# XMICRO-SERIAL_V1_1.net
KiCad netlist of a schematic drawn in EAGLE
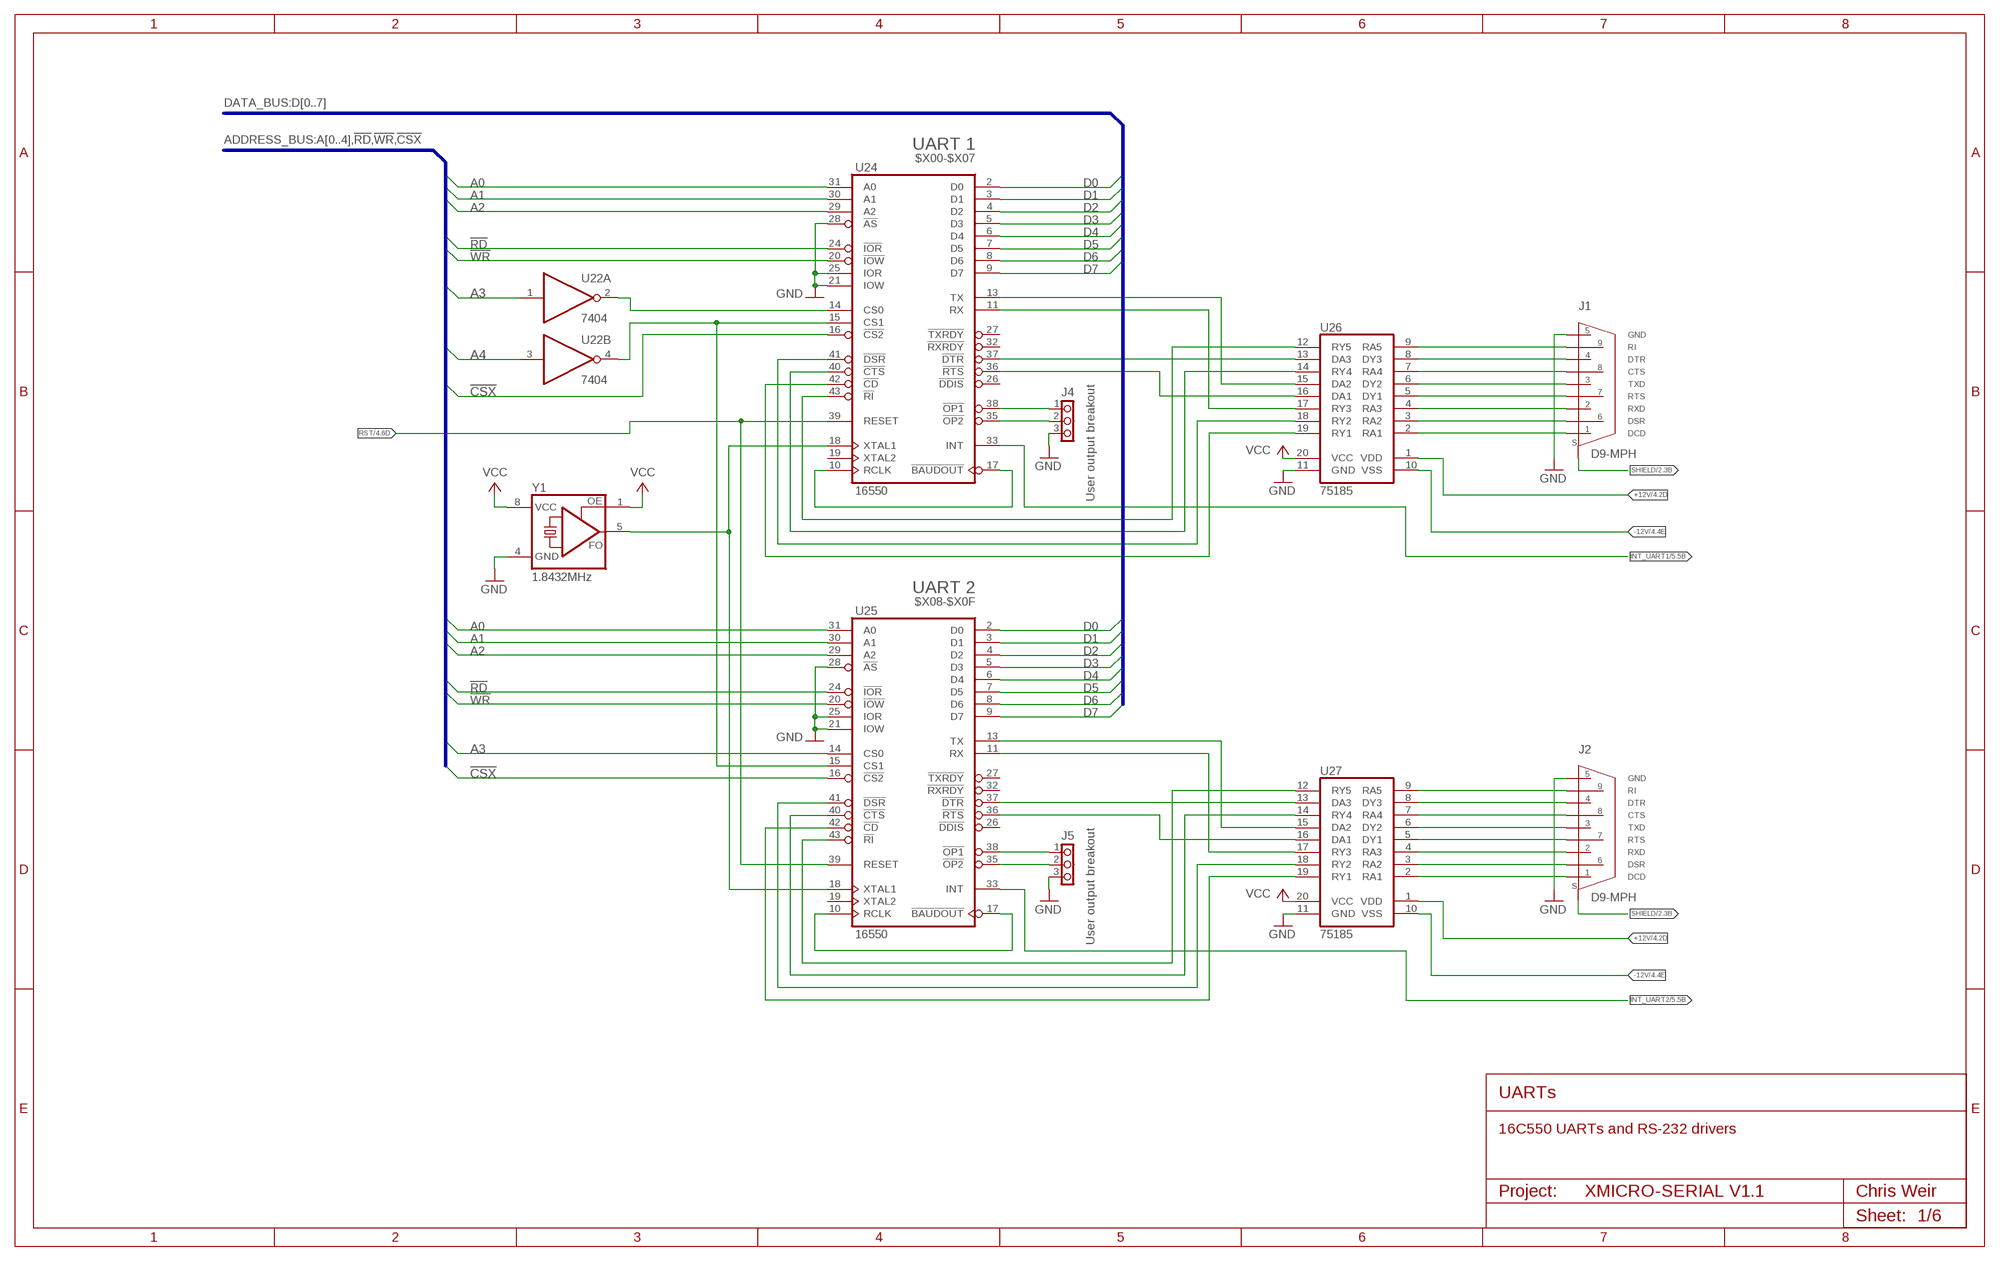
[diagram p0: schematic, sheet 1]
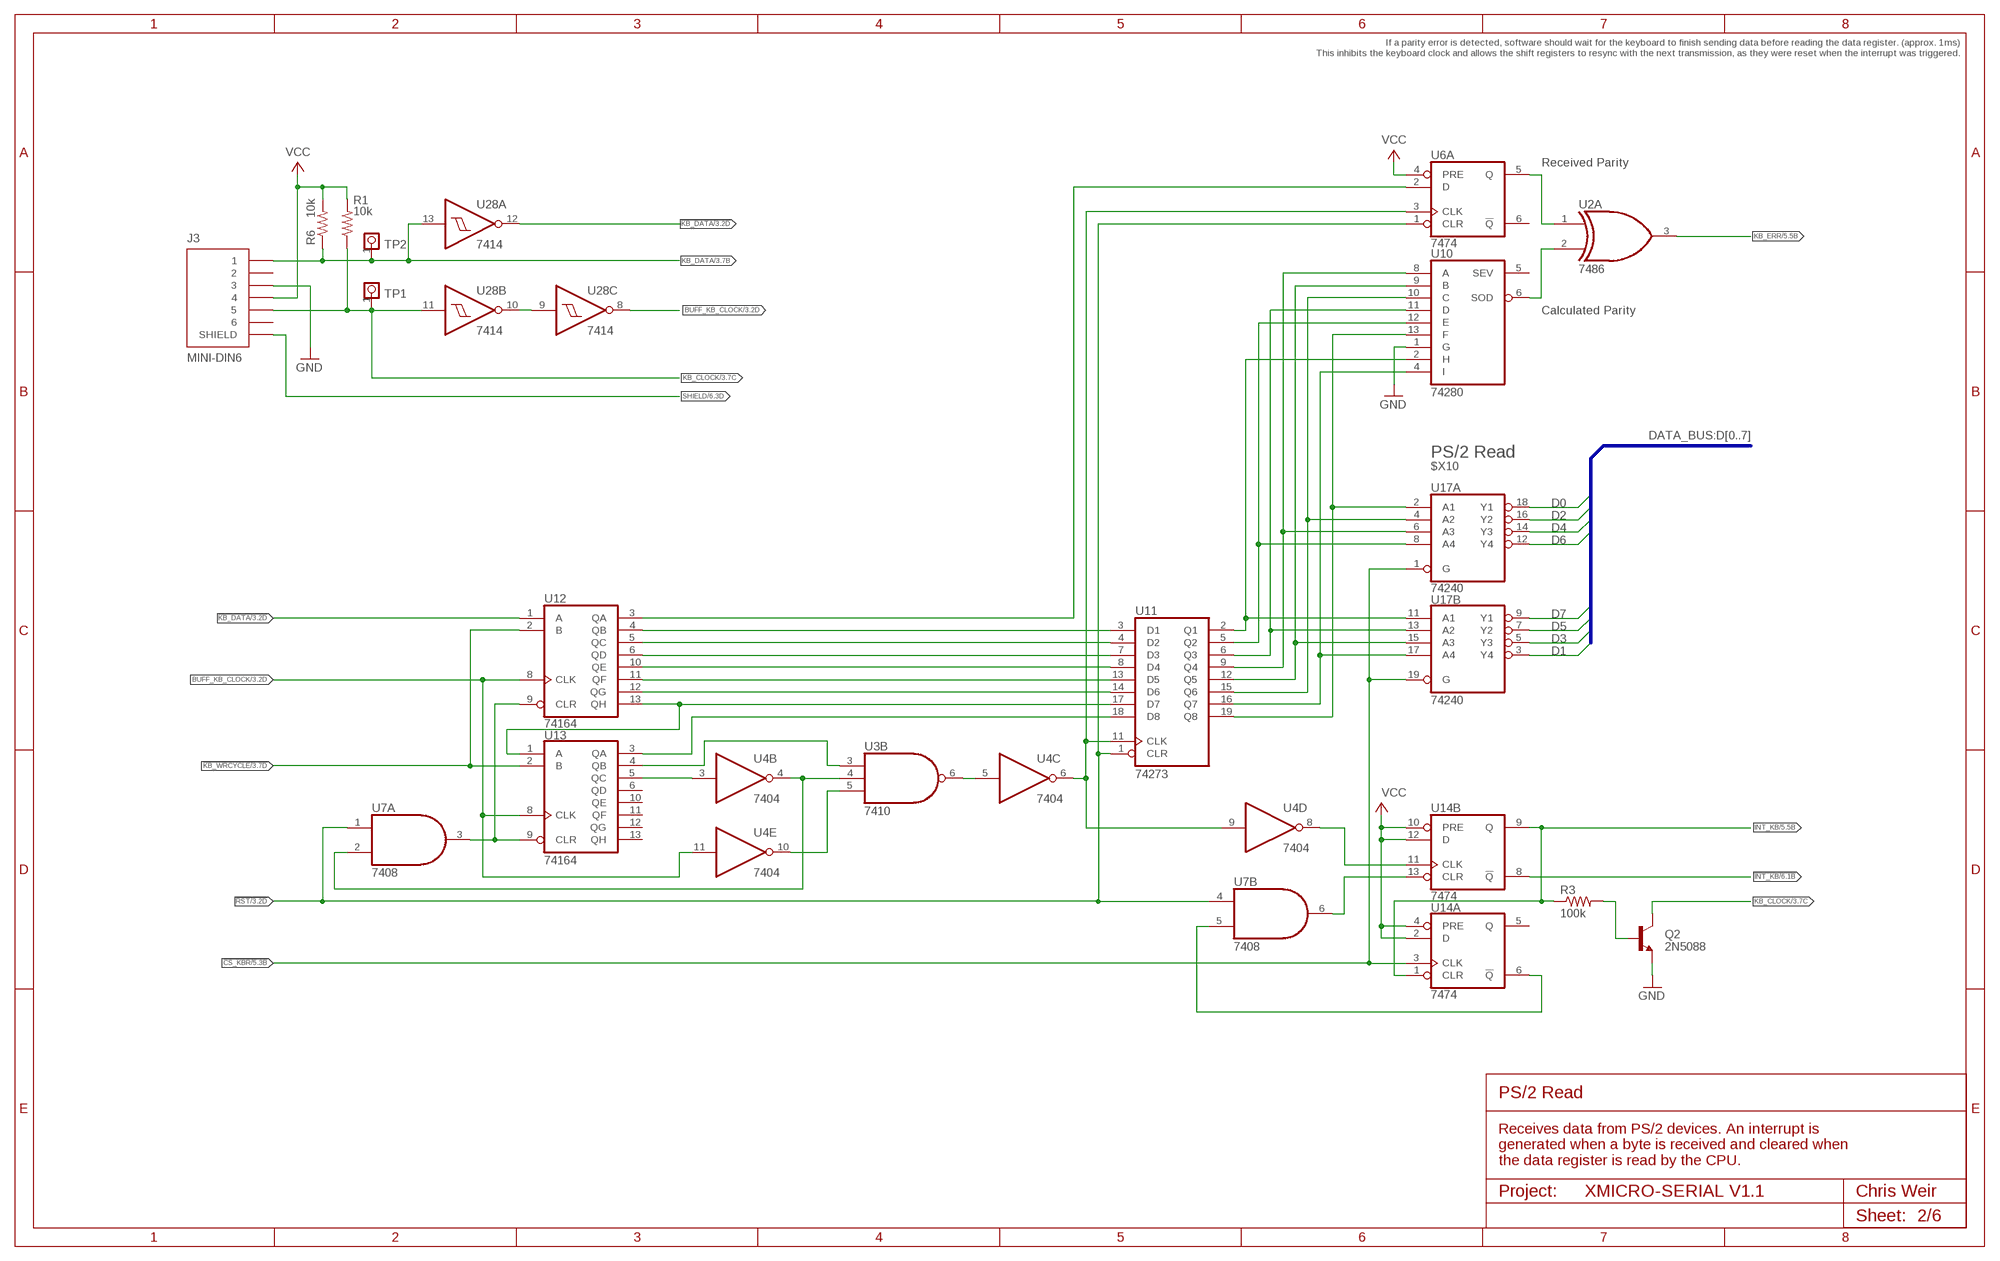
[diagram p1: schematic, sheet 2]
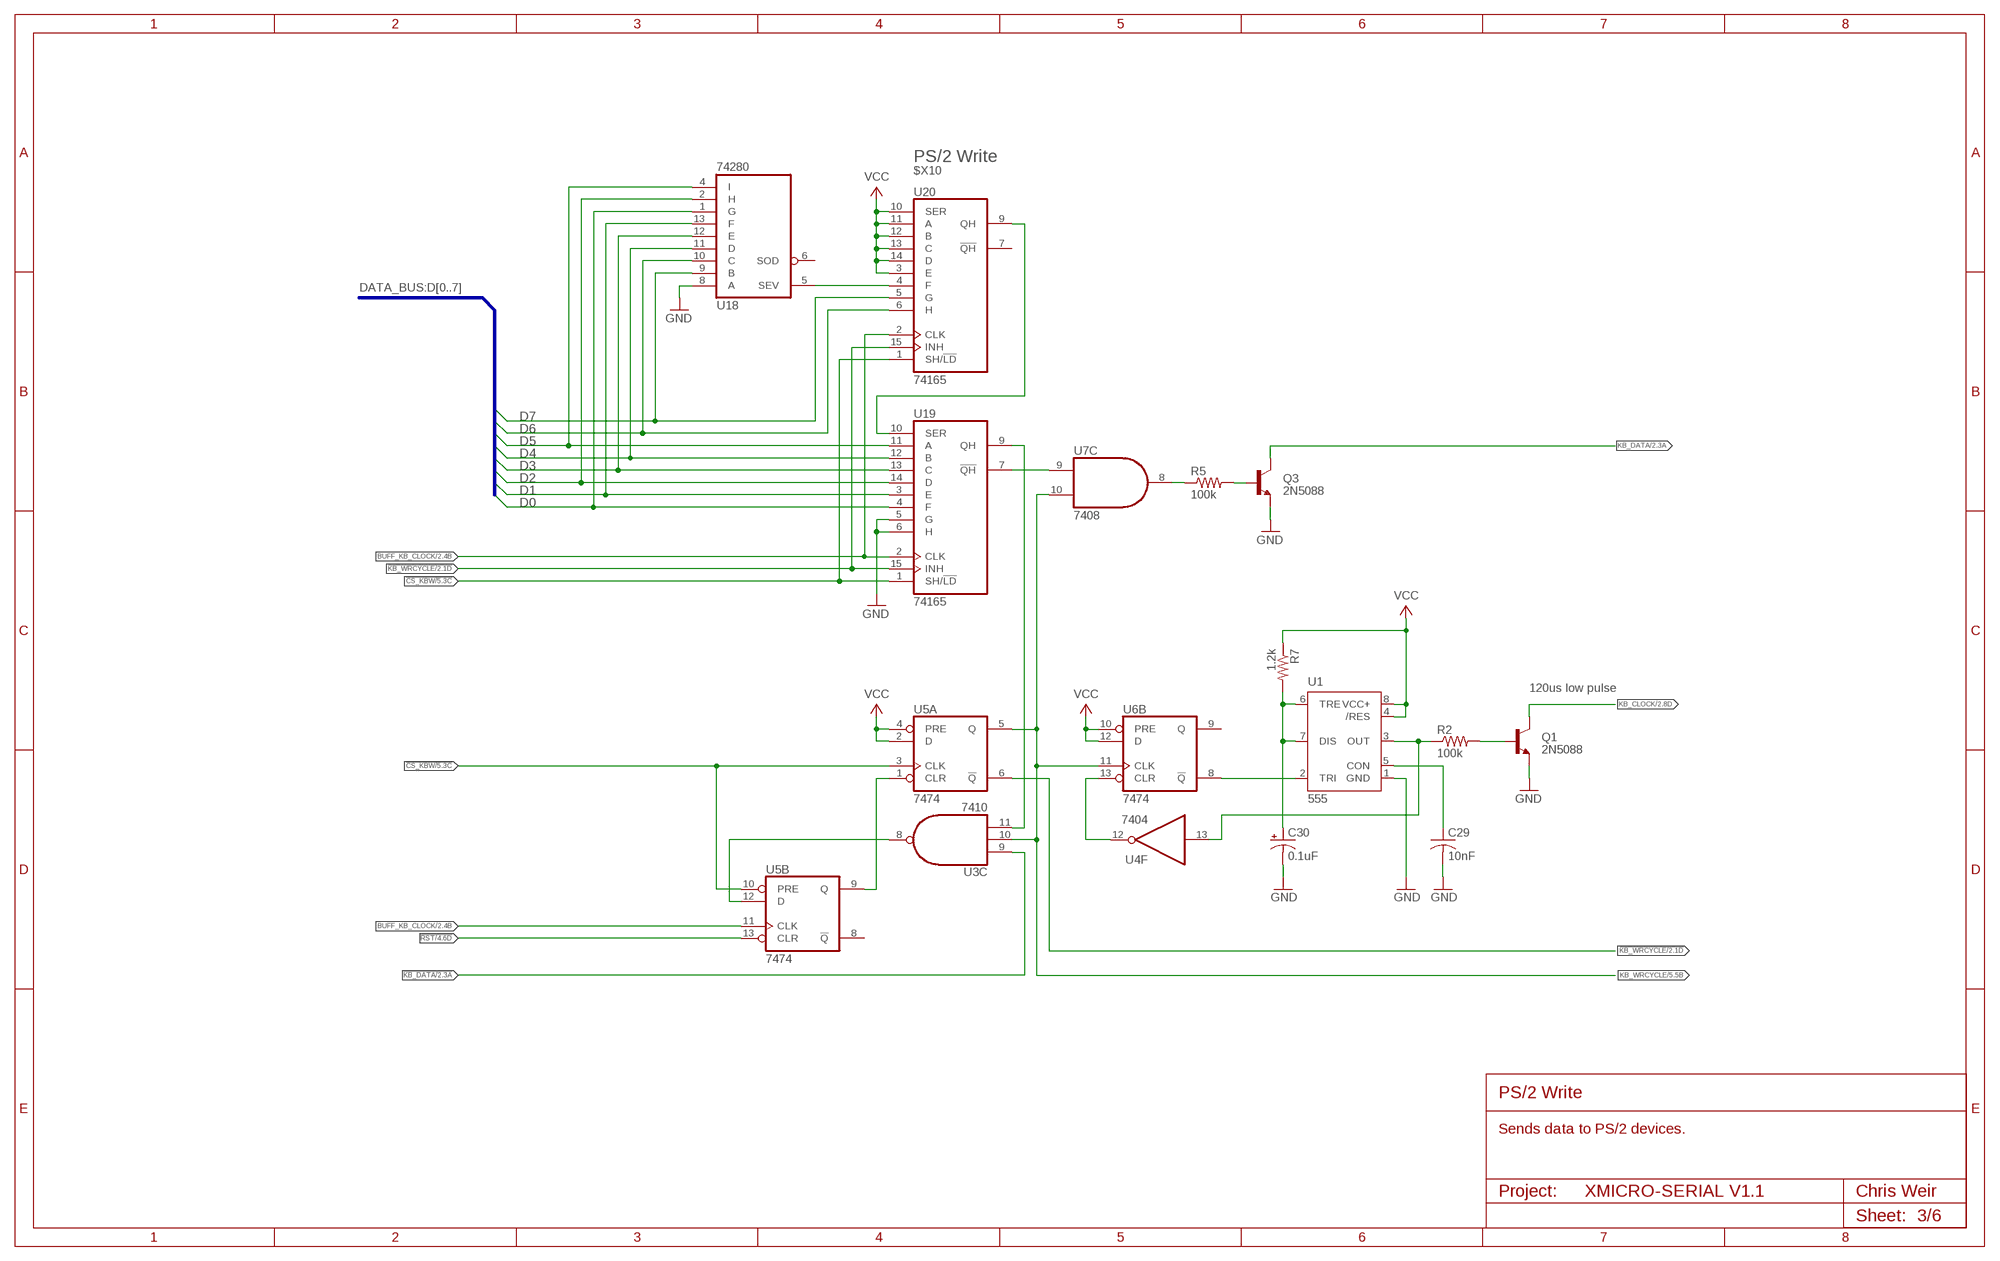
[diagram p2: schematic, sheet 3]
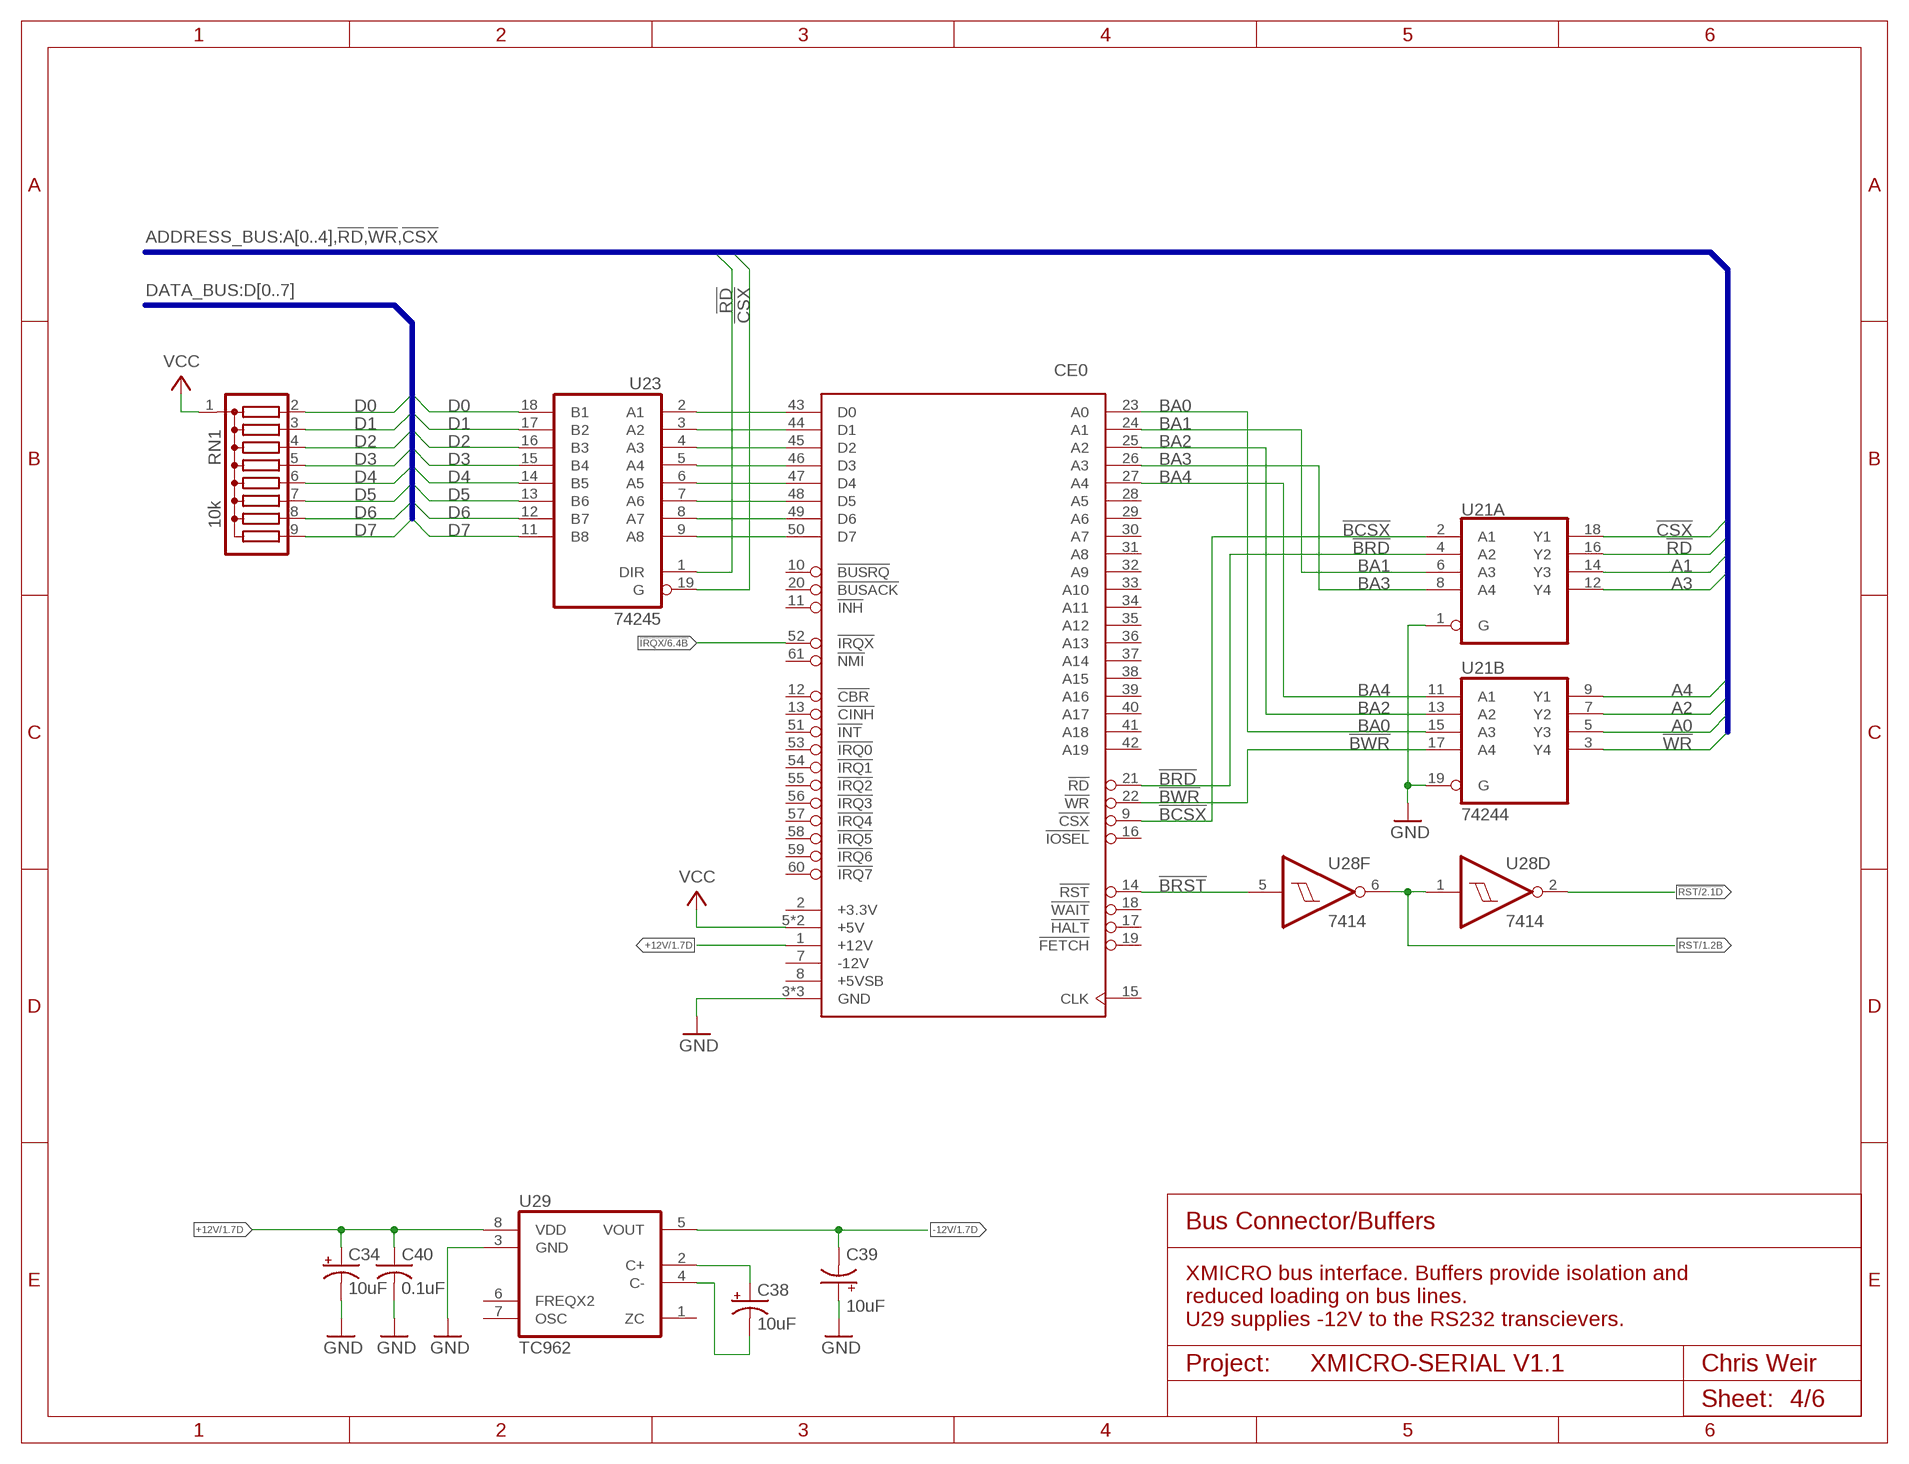
[diagram p3: schematic, sheet 4]
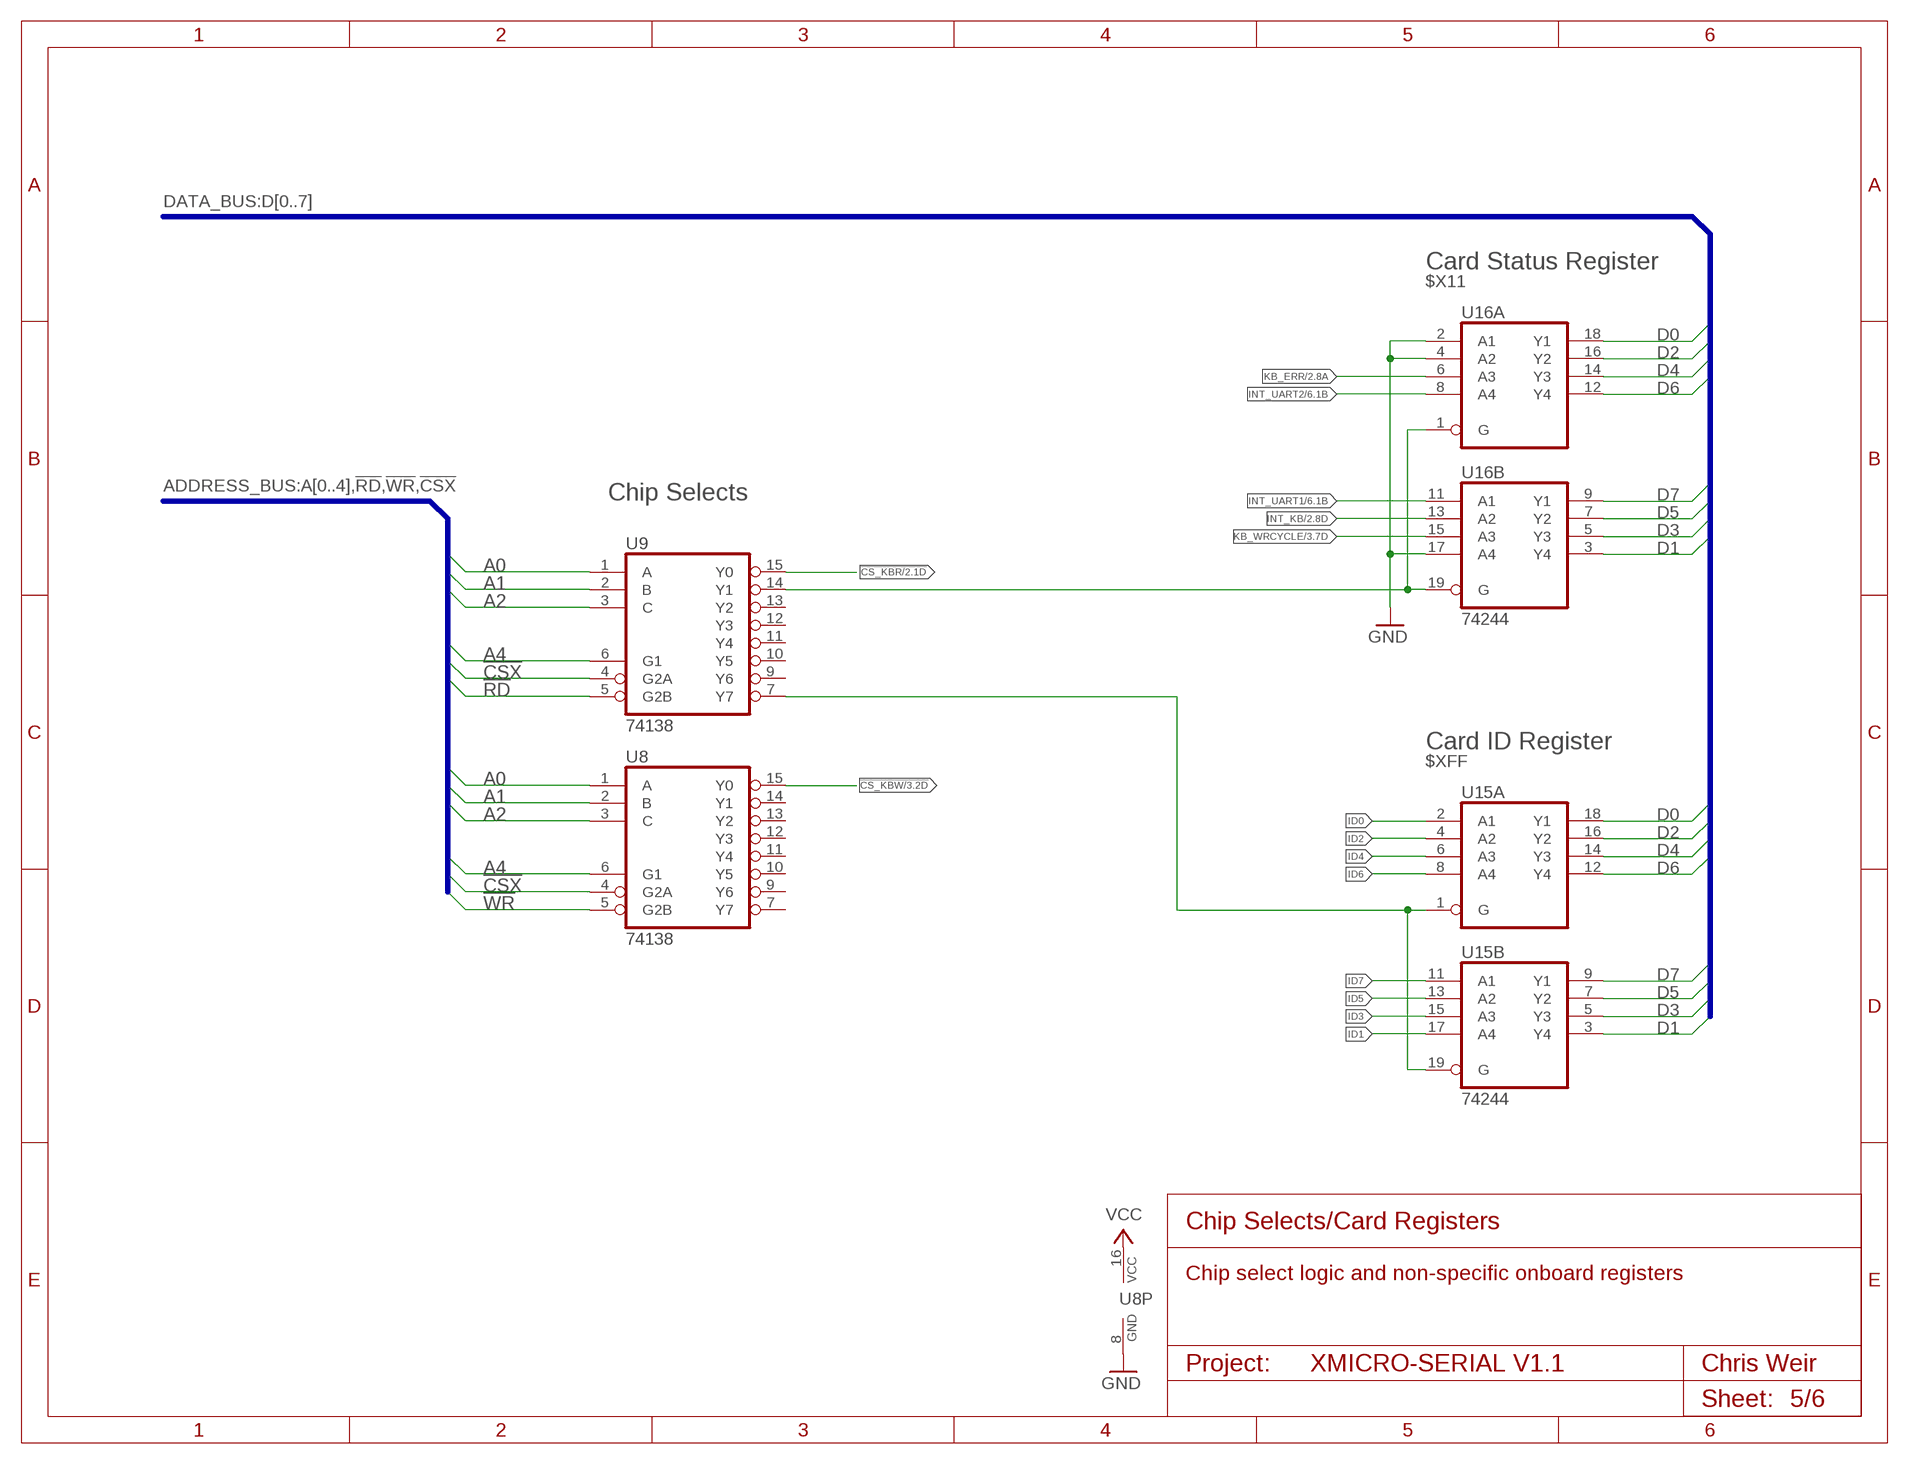
[diagram p4: schematic, sheet 5]
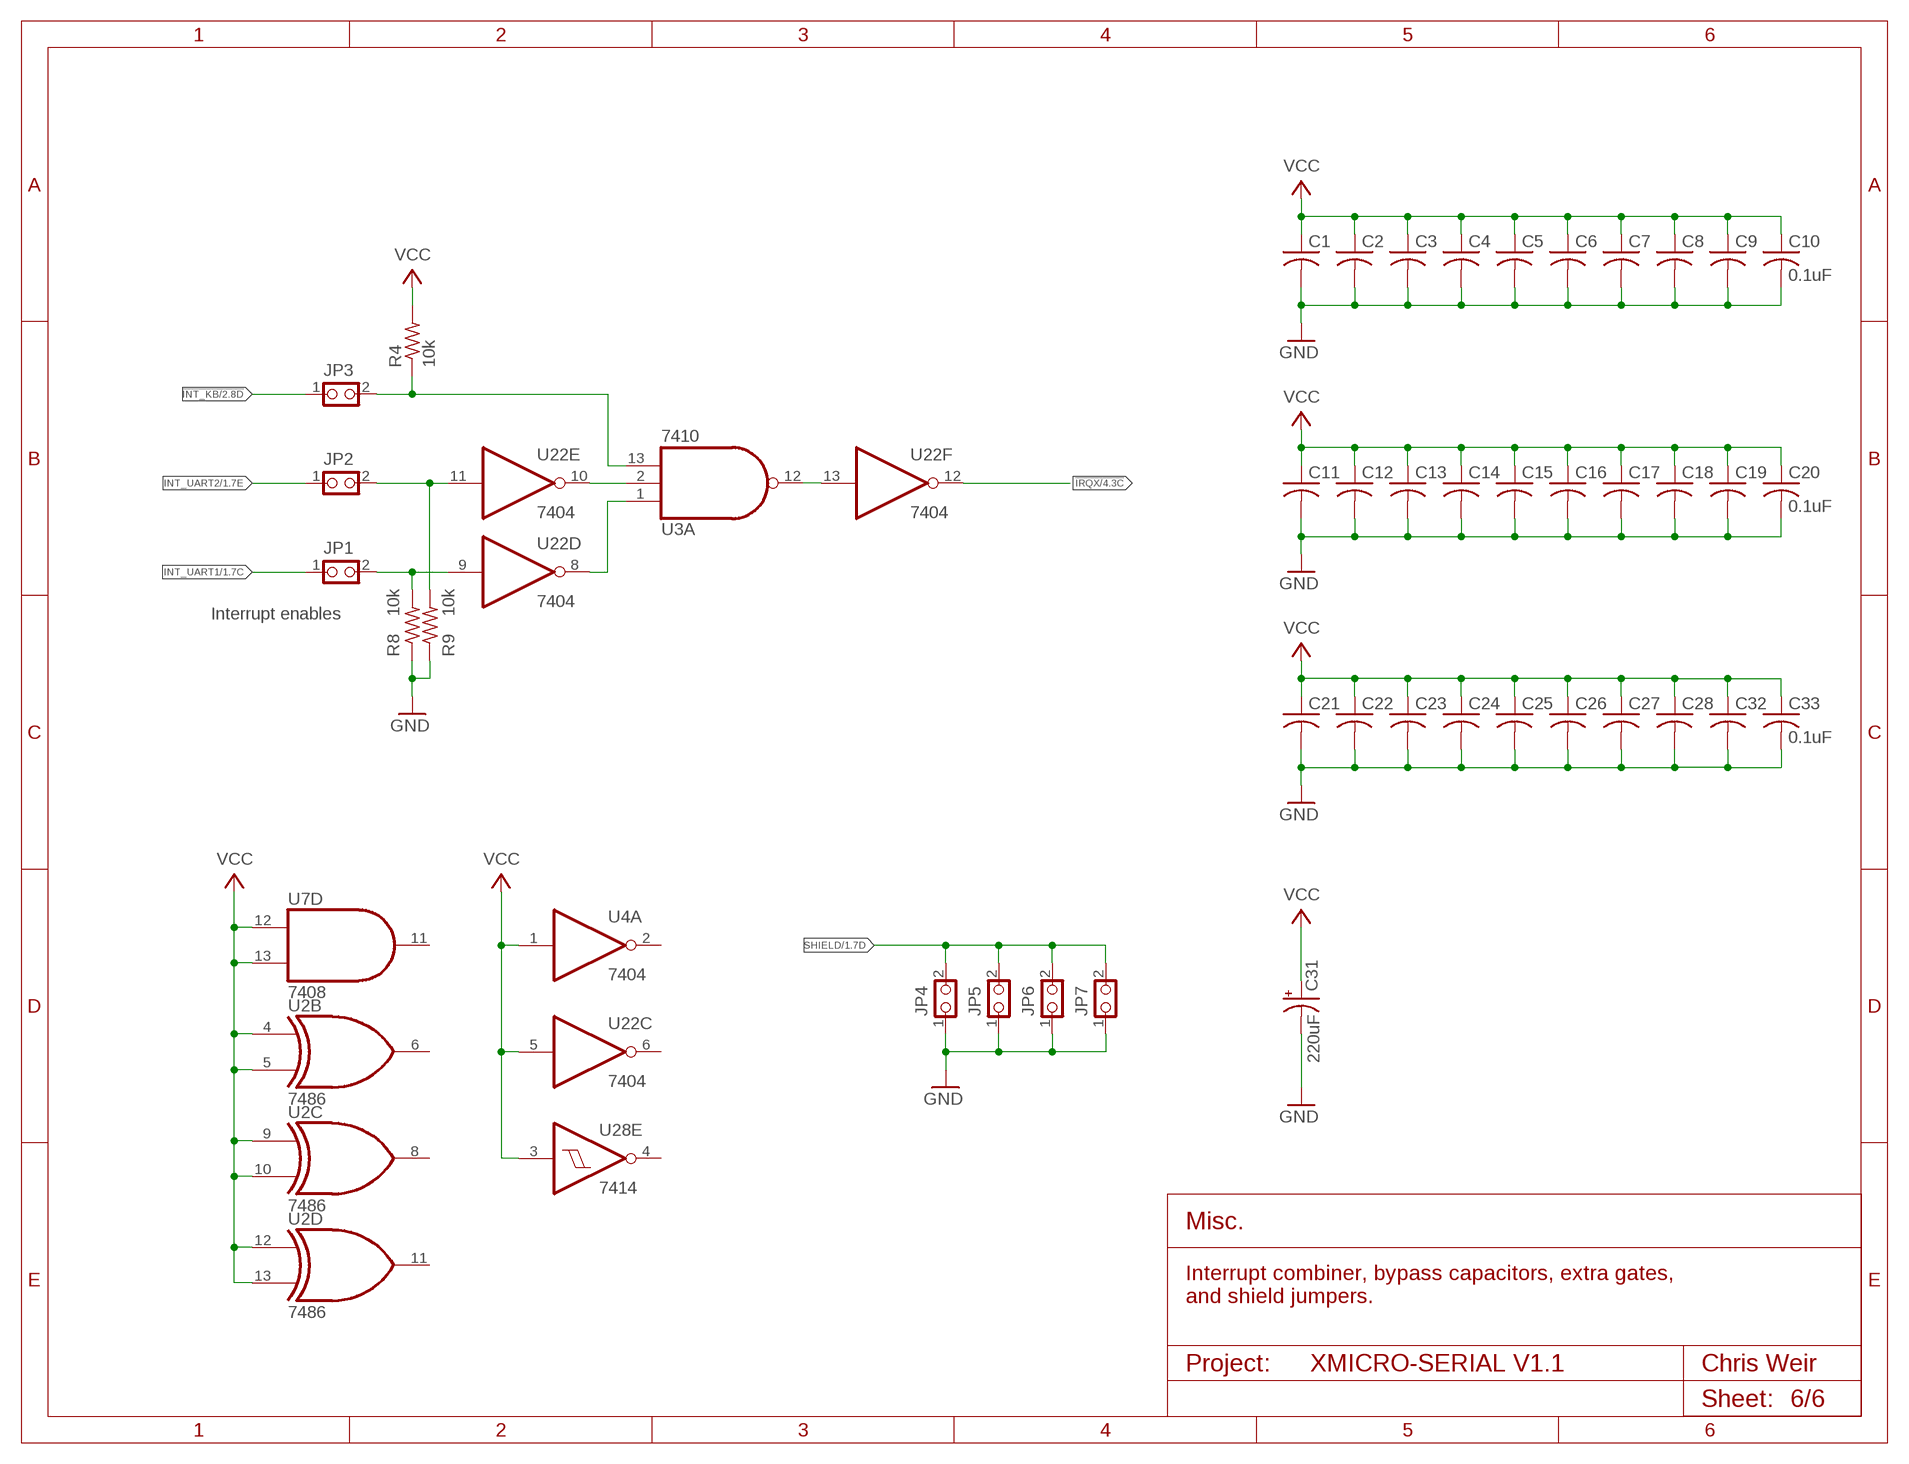
[diagram p5: schematic, sheet 6]

(export (version "E")
  (design (tool "Eeschema 10.0.6"))
  (components
    (comp (ref "C34")
      (value "10uF")
      (footprint "eagle-import:E2,5-5")
      (libsource (lib "eagle-import") (part "CPOL-USE2.5-5"))
    )
    (comp (ref "C38")
      (value "10uF")
      (footprint "eagle-import:E2,5-5")
      (libsource (lib "eagle-import") (part "CPOL-USE2.5-5"))
    )
    (comp (ref "C39")
      (value "10uF")
      (footprint "eagle-import:E2,5-5")
      (libsource (lib "eagle-import") (part "CPOL-USE2.5-5"))
    )
    (comp (ref "C40")
      (value "0.1uF")
      (footprint "eagle-import:C100")
      (libsource (lib "eagle-import") (part "C-US100"))
    )
    (comp (ref "CE0")
      (value "XMICRO-BUS-EDGE62M")
      (footprint "eagle-import:EDGE62M")
      (libsource (lib "eagle-import") (part "XMICRO-BUS-EDGE62M"))
    )
    (comp (ref "RN1")
      (value "10k")
      (footprint "eagle-import:SIL9")
      (libsource (lib "eagle-import") (part "RN8"))
    )
    (comp (ref "U21")
      (value "74244")
      (footprint "eagle-import:DIL20")
      (libsource (lib "eagle-import") (part "74244NLS"))
    )
    (comp (ref "U23")
      (value "74245")
      (footprint "eagle-import:DIL20")
      (libsource (lib "eagle-import") (part "74245NLS"))
    )
    (comp (ref "U28")
      (value "7414")
      (footprint "eagle-import:DIL14")
      (libsource (lib "eagle-import") (part "7414NLS"))
    )
    (comp (ref "U29")
      (value "TC962")
      (footprint "eagle-import:DIL8")
      (libsource (lib "eagle-import") (part "TC962"))
    )
    (comp (ref "U8")
      (value "74138")
      (footprint "eagle-import:DIL16")
      (libsource (lib "eagle-import") (part "74138NLS"))
    )
    (comp (ref "U9")
      (value "74138")
      (footprint "eagle-import:DIL16")
      (libsource (lib "eagle-import") (part "74138NLS"))
    )
    (comp (ref "U15")
      (value "74244")
      (footprint "eagle-import:DIL20")
      (libsource (lib "eagle-import") (part "74244NLS"))
    )
    (comp (ref "U16")
      (value "74244")
      (footprint "eagle-import:DIL20")
      (libsource (lib "eagle-import") (part "74244NLS"))
    )
    (comp (ref "C1")
      (value "0.1uF")
      (footprint "eagle-import:C100")
      (libsource (lib "eagle-import") (part "C-US100"))
    )
    (comp (ref "C2")
      (value "0.1uF")
      (footprint "eagle-import:C100")
      (libsource (lib "eagle-import") (part "C-US100"))
    )
    (comp (ref "C3")
      (value "0.1uF")
      (footprint "eagle-import:C100")
      (libsource (lib "eagle-import") (part "C-US100"))
    )
    (comp (ref "C4")
      (value "0.1uF")
      (footprint "eagle-import:C100")
      (libsource (lib "eagle-import") (part "C-US100"))
    )
    (comp (ref "C5")
      (value "0.1uF")
      (footprint "eagle-import:C100")
      (libsource (lib "eagle-import") (part "C-US100"))
    )
    (comp (ref "C6")
      (value "0.1uF")
      (footprint "eagle-import:C100")
      (libsource (lib "eagle-import") (part "C-US100"))
    )
    (comp (ref "C7")
      (value "0.1uF")
      (footprint "eagle-import:C100")
      (libsource (lib "eagle-import") (part "C-US100"))
    )
    (comp (ref "C8")
      (value "0.1uF")
      (footprint "eagle-import:C100")
      (libsource (lib "eagle-import") (part "C-US100"))
    )
    (comp (ref "C9")
      (value "0.1uF")
      (footprint "eagle-import:C100")
      (libsource (lib "eagle-import") (part "C-US100"))
    )
    (comp (ref "C10")
      (value "0.1uF")
      (footprint "eagle-import:C100")
      (libsource (lib "eagle-import") (part "C-US100"))
    )
    (comp (ref "C11")
      (value "0.1uF")
      (footprint "eagle-import:C100")
      (libsource (lib "eagle-import") (part "C-US100"))
    )
    (comp (ref "C12")
      (value "0.1uF")
      (footprint "eagle-import:C100")
      (libsource (lib "eagle-import") (part "C-US100"))
    )
    (comp (ref "C13")
      (value "0.1uF")
      (footprint "eagle-import:C100")
      (libsource (lib "eagle-import") (part "C-US100"))
    )
    (comp (ref "C14")
      (value "0.1uF")
      (footprint "eagle-import:C100")
      (libsource (lib "eagle-import") (part "C-US100"))
    )
    (comp (ref "C15")
      (value "0.1uF")
      (footprint "eagle-import:C100")
      (libsource (lib "eagle-import") (part "C-US100"))
    )
    (comp (ref "C16")
      (value "0.1uF")
      (footprint "eagle-import:C100")
      (libsource (lib "eagle-import") (part "C-US100"))
    )
    (comp (ref "C17")
      (value "0.1uF")
      (footprint "eagle-import:C100")
      (libsource (lib "eagle-import") (part "C-US100"))
    )
    (comp (ref "C18")
      (value "0.1uF")
      (footprint "eagle-import:C100")
      (libsource (lib "eagle-import") (part "C-US100"))
    )
    (comp (ref "C19")
      (value "0.1uF")
      (footprint "eagle-import:C100")
      (libsource (lib "eagle-import") (part "C-US100"))
    )
    (comp (ref "C20")
      (value "0.1uF")
      (footprint "eagle-import:C100")
      (libsource (lib "eagle-import") (part "C-US100"))
    )
    (comp (ref "C21")
      (value "0.1uF")
      (footprint "eagle-import:C100")
      (libsource (lib "eagle-import") (part "C-US100"))
    )
    (comp (ref "C22")
      (value "0.1uF")
      (footprint "eagle-import:C100")
      (libsource (lib "eagle-import") (part "C-US100"))
    )
    (comp (ref "C23")
      (value "0.1uF")
      (footprint "eagle-import:C100")
      (libsource (lib "eagle-import") (part "C-US100"))
    )
    (comp (ref "C24")
      (value "0.1uF")
      (footprint "eagle-import:C100")
      (libsource (lib "eagle-import") (part "C-US100"))
    )
    (comp (ref "C25")
      (value "0.1uF")
      (footprint "eagle-import:C100")
      (libsource (lib "eagle-import") (part "C-US100"))
    )
    (comp (ref "C26")
      (value "0.1uF")
      (footprint "eagle-import:C100")
      (libsource (lib "eagle-import") (part "C-US100"))
    )
    (comp (ref "C27")
      (value "0.1uF")
      (footprint "eagle-import:C100")
      (libsource (lib "eagle-import") (part "C-US100"))
    )
    (comp (ref "C28")
      (value "0.1uF")
      (footprint "eagle-import:C100")
      (libsource (lib "eagle-import") (part "C-US100"))
    )
    (comp (ref "C31")
      (value "220uF")
      (footprint "eagle-import:C-10-5")
      (libsource (lib "eagle-import") (part "CPOL-US-10-5"))
    )
    (comp (ref "C32")
      (value "0.1uF")
      (footprint "eagle-import:C100")
      (libsource (lib "eagle-import") (part "C-US100"))
    )
    (comp (ref "C33")
      (value "0.1uF")
      (footprint "eagle-import:C100")
      (libsource (lib "eagle-import") (part "C-US100"))
    )
    (comp (ref "JP1")
      (value "PINHD-1X2THRU")
      (footprint "eagle-import:1X02")
      (libsource (lib "eagle-import") (part "PINHD-1X2THRU"))
    )
    (comp (ref "JP2")
      (value "PINHD-1X2THRU")
      (footprint "eagle-import:1X02")
      (libsource (lib "eagle-import") (part "PINHD-1X2THRU"))
    )
    (comp (ref "JP3")
      (value "PINHD-1X2THRU")
      (footprint "eagle-import:1X02")
      (libsource (lib "eagle-import") (part "PINHD-1X2THRU"))
    )
    (comp (ref "JP4")
      (value "PINHD-1X2THRU")
      (footprint "eagle-import:1X02")
      (libsource (lib "eagle-import") (part "PINHD-1X2THRU"))
    )
    (comp (ref "JP5")
      (value "PINHD-1X2THRU")
      (footprint "eagle-import:1X02")
      (libsource (lib "eagle-import") (part "PINHD-1X2THRU"))
    )
    (comp (ref "JP6")
      (value "PINHD-1X2THRU")
      (footprint "eagle-import:1X02")
      (libsource (lib "eagle-import") (part "PINHD-1X2THRU"))
    )
    (comp (ref "JP7")
      (value "PINHD-1X2THRU")
      (footprint "eagle-import:1X02")
      (libsource (lib "eagle-import") (part "PINHD-1X2THRU"))
    )
    (comp (ref "R4")
      (value "10k")
      (footprint "eagle-import:0207_10")
      (libsource (lib "eagle-import") (part "R-US_0207/10"))
    )
    (comp (ref "R8")
      (value "10k")
      (footprint "eagle-import:0207_10")
      (libsource (lib "eagle-import") (part "R-US_0207/10"))
    )
    (comp (ref "R9")
      (value "10k")
      (footprint "eagle-import:0207_10")
      (libsource (lib "eagle-import") (part "R-US_0207/10"))
    )
    (comp (ref "U2")
      (value "7486")
      (footprint "eagle-import:DIL14")
      (libsource (lib "eagle-import") (part "7486NLS"))
    )
    (comp (ref "U3")
      (value "7410")
      (footprint "eagle-import:DIL14")
      (libsource (lib "eagle-import") (part "7410NLS"))
    )
    (comp (ref "U4")
      (value "7404")
      (footprint "eagle-import:DIL14")
      (libsource (lib "eagle-import") (part "74xx-us_7404NLS"))
    )
    (comp (ref "U7")
      (value "7408")
      (footprint "eagle-import:DIL14")
      (libsource (lib "eagle-import") (part "7408NLS"))
    )
    (comp (ref "U22")
      (value "7404")
      (footprint "eagle-import:DIL14")
      (libsource (lib "eagle-import") (part "7404NLS"))
    )
    (comp (ref "C29")
      (value "10nF")
      (footprint "eagle-import:C100")
      (libsource (lib "eagle-import") (part "C-US100"))
    )
    (comp (ref "C30")
      (value "0.1uF")
      (footprint "eagle-import:E2,5-6")
      (libsource (lib "eagle-import") (part "CPOL-USE2.5-6"))
    )
    (comp (ref "Q1")
      (value "2N5088")
      (footprint "eagle-import:TO92")
      (libsource (lib "eagle-import") (part "TRANSISTOR-NPN-2N5088"))
    )
    (comp (ref "Q3")
      (value "2N5088")
      (footprint "eagle-import:TO92")
      (libsource (lib "eagle-import") (part "TRANSISTOR-NPN-2N5088"))
    )
    (comp (ref "R2")
      (value "100k")
      (footprint "eagle-import:0207_10")
      (libsource (lib "eagle-import") (part "R-US_0207/10"))
    )
    (comp (ref "R5")
      (value "100k")
      (footprint "eagle-import:0207_10")
      (libsource (lib "eagle-import") (part "R-US_0207/10"))
    )
    (comp (ref "R7")
      (value "1.2k")
      (footprint "eagle-import:0207_10")
      (libsource (lib "eagle-import") (part "R-US_0207/10"))
    )
    (comp (ref "U1")
      (value "555")
      (footprint "eagle-import:DIL-08")
      (fields (field (name "MF") "Arrow Electronics") (field (name "MPN") "NE555N"))
      (libsource (lib "eagle-import") (part "NE555"))
    )
    (comp (ref "U5")
      (value "7474")
      (footprint "eagle-import:DIL14")
      (libsource (lib "eagle-import") (part "7474NLS"))
    )
    (comp (ref "U6")
      (value "7474")
      (footprint "eagle-import:DIL14")
      (libsource (lib "eagle-import") (part "7474NLS"))
    )
    (comp (ref "U18")
      (value "74280")
      (footprint "eagle-import:DIL14")
      (libsource (lib "eagle-import") (part "74280NLS"))
    )
    (comp (ref "U19")
      (value "74165")
      (footprint "eagle-import:DIL16")
      (libsource (lib "eagle-import") (part "74165NLS"))
    )
    (comp (ref "U20")
      (value "74165")
      (footprint "eagle-import:DIL16")
      (libsource (lib "eagle-import") (part "74165NLS"))
    )
    (comp (ref "J3")
      (value "MINI-DIN6")
      (footprint "eagle-import:MINI-DIN6")
      (libsource (lib "eagle-import") (part "MINI-DIN6"))
    )
    (comp (ref "Q2")
      (value "2N5088")
      (footprint "eagle-import:TO92")
      (libsource (lib "eagle-import") (part "TRANSISTOR-NPN-2N5088"))
    )
    (comp (ref "R1")
      (value "10k")
      (footprint "eagle-import:0207_10")
      (libsource (lib "eagle-import") (part "R-US_0207/10"))
    )
    (comp (ref "R3")
      (value "100k")
      (footprint "eagle-import:0207_10")
      (libsource (lib "eagle-import") (part "R-US_0207/10"))
    )
    (comp (ref "R6")
      (value "10k")
      (footprint "eagle-import:0207_10")
      (libsource (lib "eagle-import") (part "R-US_0207/10"))
    )
    (comp (ref "TP1")
      (value "PINHD-1X1")
      (footprint "eagle-import:1X01")
      (libsource (lib "eagle-import") (part "PINHD-1X1"))
    )
    (comp (ref "TP2")
      (value "PINHD-1X1")
      (footprint "eagle-import:1X01")
      (libsource (lib "eagle-import") (part "PINHD-1X1"))
    )
    (comp (ref "U10")
      (value "74280")
      (footprint "eagle-import:DIL14")
      (libsource (lib "eagle-import") (part "74280NLS"))
    )
    (comp (ref "U11")
      (value "74273")
      (footprint "eagle-import:DIL20")
      (libsource (lib "eagle-import") (part "74273N"))
    )
    (comp (ref "U12")
      (value "74164")
      (footprint "eagle-import:DIL14")
      (libsource (lib "eagle-import") (part "74164NHCT"))
    )
    (comp (ref "U13")
      (value "74164")
      (footprint "eagle-import:DIL14")
      (libsource (lib "eagle-import") (part "74164NHCT"))
    )
    (comp (ref "U14")
      (value "7474")
      (footprint "eagle-import:DIL14")
      (libsource (lib "eagle-import") (part "7474NLS"))
    )
    (comp (ref "U17")
      (value "74240")
      (footprint "eagle-import:DIL20")
      (libsource (lib "eagle-import") (part "74240NLS"))
    )
    (comp (ref "J1")
      (value "D9-MPH")
      (footprint "eagle-import:D9-H")
      (libsource (lib "eagle-import") (part "D9-MPH"))
    )
    (comp (ref "J2")
      (value "D9-MPH")
      (footprint "eagle-import:D9-H")
      (libsource (lib "eagle-import") (part "D9-MPH"))
    )
    (comp (ref "J4")
      (value "PINHD1X3")
      (footprint "eagle-import:1X03")
      (libsource (lib "eagle-import") (part "PINHD1X3"))
    )
    (comp (ref "J5")
      (value "PINHD1X3")
      (footprint "eagle-import:1X03")
      (libsource (lib "eagle-import") (part "PINHD1X3"))
    )
    (comp (ref "U24")
      (value "16550")
      (footprint "eagle-import:S44")
      (libsource (lib "eagle-import") (part "16C550S44"))
    )
    (comp (ref "U25")
      (value "16550")
      (footprint "eagle-import:S44")
      (libsource (lib "eagle-import") (part "16C550S44"))
    )
    (comp (ref "U26")
      (value "75185")
      (footprint "eagle-import:DIL20")
      (libsource (lib "eagle-import") (part "75C185N"))
    )
    (comp (ref "U27")
      (value "75185")
      (footprint "eagle-import:DIL20")
      (libsource (lib "eagle-import") (part "75C185N"))
    )
    (comp (ref "Y1")
      (value "1.8432MHz")
      (footprint "eagle-import:DIL08S")
      (libsource (lib "eagle-import") (part "OSC-OE"))
    )
  )
  (nets
    (net (code "41") (name "+12V") (class "Default")
      (node (ref "C34") (pin "+") (pinfunction "+_+") (pintype "passive"))
      (node (ref "C40") (pin "P$1") (pinfunction "1_P$1") (pintype "passive"))
      (node (ref "CE0") (pin "1") (pinfunction "+12V_1") (pintype "bidirectional"))
      (node (ref "U26") (pin "1") (pinfunction "VDD_1") (pintype "power_in"))
      (node (ref "U27") (pin "1") (pinfunction "VDD_1") (pintype "power_in"))
      (node (ref "U29") (pin "8") (pinfunction "VDD_8") (pintype "input"))
    )
    (net (code "42") (name "-12V") (class "Default")
      (node (ref "C39") (pin "-") (pinfunction "-_-") (pintype "passive"))
      (node (ref "U26") (pin "10") (pinfunction "VSS_10") (pintype "power_in"))
      (node (ref "U27") (pin "10") (pinfunction "VSS_10") (pintype "power_in"))
      (node (ref "U29") (pin "5") (pinfunction "VOUT_5") (pintype "output"))
    )
    (net (code "51") (name "A0") (class "Default")
      (node (ref "U21") (pin "5") (pinfunction "Y3_5") (pintype "tri_state"))
      (node (ref "U24") (pin "31") (pinfunction "A0_31") (pintype "input"))
      (node (ref "U25") (pin "31") (pinfunction "A0_31") (pintype "input"))
      (node (ref "U8") (pin "1") (pinfunction "A_1") (pintype "input"))
      (node (ref "U9") (pin "1") (pinfunction "A_1") (pintype "input"))
    )
    (net (code "52") (name "A1") (class "Default")
      (node (ref "U21") (pin "14") (pinfunction "Y3_14") (pintype "tri_state"))
      (node (ref "U24") (pin "30") (pinfunction "A1_30") (pintype "input"))
      (node (ref "U25") (pin "30") (pinfunction "A1_30") (pintype "input"))
      (node (ref "U8") (pin "2") (pinfunction "B_2") (pintype "input"))
      (node (ref "U9") (pin "2") (pinfunction "B_2") (pintype "input"))
    )
    (net (code "53") (name "A2") (class "Default")
      (node (ref "U21") (pin "7") (pinfunction "Y2_7") (pintype "tri_state"))
      (node (ref "U24") (pin "29") (pinfunction "A2_29") (pintype "input"))
      (node (ref "U25") (pin "29") (pinfunction "A2_29") (pintype "input"))
      (node (ref "U8") (pin "3") (pinfunction "C_3") (pintype "input"))
      (node (ref "U9") (pin "3") (pinfunction "C_3") (pintype "input"))
    )
    (net (code "54") (name "A3") (class "Default")
      (node (ref "U21") (pin "12") (pinfunction "Y4_12") (pintype "tri_state"))
      (node (ref "U22") (pin "1") (pinfunction "I_1") (pintype "input"))
      (node (ref "U25") (pin "14") (pinfunction "CS0_14") (pintype "input"))
    )
    (net (code "55") (name "A4") (class "Default")
      (node (ref "U21") (pin "9") (pinfunction "Y1_9") (pintype "tri_state"))
      (node (ref "U22") (pin "3") (pinfunction "I_3") (pintype "input"))
      (node (ref "U8") (pin "6") (pinfunction "G1_6") (pintype "input"))
      (node (ref "U9") (pin "6") (pinfunction "G1_6") (pintype "input"))
    )
    (net (code "56") (name "BA0") (class "Default")
      (node (ref "CE0") (pin "23") (pinfunction "A0_23") (pintype "bidirectional"))
      (node (ref "U21") (pin "15") (pinfunction "A3_15") (pintype "input"))
    )
    (net (code "57") (name "BA1") (class "Default")
      (node (ref "CE0") (pin "24") (pinfunction "A1_24") (pintype "bidirectional"))
      (node (ref "U21") (pin "6") (pinfunction "A3_6") (pintype "input"))
    )
    (net (code "58") (name "BA2") (class "Default")
      (node (ref "CE0") (pin "25") (pinfunction "A2_25") (pintype "bidirectional"))
      (node (ref "U21") (pin "13") (pinfunction "A2_13") (pintype "input"))
    )
    (net (code "59") (name "BA3") (class "Default")
      (node (ref "CE0") (pin "26") (pinfunction "A3_26") (pintype "bidirectional"))
      (node (ref "U21") (pin "8") (pinfunction "A4_8") (pintype "input"))
    )
    (net (code "60") (name "BA4") (class "Default")
      (node (ref "CE0") (pin "27") (pinfunction "A4_27") (pintype "bidirectional"))
      (node (ref "U21") (pin "11") (pinfunction "A1_11") (pintype "input"))
    )
    (net (code "61") (name "BUFF_KB_CLOCK") (class "Default")
      (node (ref "U12") (pin "8") (pinfunction "CLK_8") (pintype "input"))
      (node (ref "U13") (pin "8") (pinfunction "CLK_8") (pintype "input"))
      (node (ref "U19") (pin "2") (pinfunction "CLK_2") (pintype "input"))
      (node (ref "U20") (pin "2") (pinfunction "CLK_2") (pintype "input"))
      (node (ref "U28") (pin "8") (pinfunction "O_8") (pintype "output"))
      (node (ref "U4") (pin "11") (pinfunction "I_11") (pintype "input"))
      (node (ref "U5") (pin "11") (pinfunction "CLK_11") (pintype "input"))
    )
    (net (code "62") (name "D0") (class "Default")
      (node (ref "RN1") (pin "2") (pinfunction "2_2") (pintype "passive"))
      (node (ref "U15") (pin "18") (pinfunction "Y1_18") (pintype "tri_state"))
      (node (ref "U16") (pin "18") (pinfunction "Y1_18") (pintype "tri_state"))
      (node (ref "U17") (pin "18") (pinfunction "Y1_18") (pintype "tri_state"))
      (node (ref "U18") (pin "1") (pinfunction "G_1") (pintype "input"))
      (node (ref "U19") (pin "4") (pinfunction "F_4") (pintype "input"))
      (node (ref "U23") (pin "18") (pinfunction "B1_18") (pintype "bidirectional"))
      (node (ref "U24") (pin "2") (pinfunction "D0_2") (pintype "tri_state"))
      (node (ref "U25") (pin "2") (pinfunction "D0_2") (pintype "tri_state"))
    )
    (net (code "63") (name "D1") (class "Default")
      (node (ref "RN1") (pin "3") (pinfunction "3_3") (pintype "passive"))
      (node (ref "U15") (pin "3") (pinfunction "Y4_3") (pintype "tri_state"))
      (node (ref "U16") (pin "3") (pinfunction "Y4_3") (pintype "tri_state"))
      (node (ref "U17") (pin "3") (pinfunction "Y4_3") (pintype "tri_state"))
      (node (ref "U18") (pin "13") (pinfunction "F_13") (pintype "input"))
      (node (ref "U19") (pin "3") (pinfunction "E_3") (pintype "input"))
      (node (ref "U23") (pin "17") (pinfunction "B2_17") (pintype "bidirectional"))
      (node (ref "U24") (pin "3") (pinfunction "D1_3") (pintype "tri_state"))
      (node (ref "U25") (pin "3") (pinfunction "D1_3") (pintype "tri_state"))
    )
    (net (code "64") (name "D2") (class "Default")
      (node (ref "RN1") (pin "4") (pinfunction "4_4") (pintype "passive"))
      (node (ref "U15") (pin "16") (pinfunction "Y2_16") (pintype "tri_state"))
      (node (ref "U16") (pin "16") (pinfunction "Y2_16") (pintype "tri_state"))
      (node (ref "U17") (pin "16") (pinfunction "Y2_16") (pintype "tri_state"))
      (node (ref "U18") (pin "2") (pinfunction "H_2") (pintype "input"))
      (node (ref "U19") (pin "14") (pinfunction "D_14") (pintype "input"))
      (node (ref "U23") (pin "16") (pinfunction "B3_16") (pintype "bidirectional"))
      (node (ref "U24") (pin "4") (pinfunction "D2_4") (pintype "tri_state"))
      (node (ref "U25") (pin "4") (pinfunction "D2_4") (pintype "tri_state"))
    )
    (net (code "65") (name "D3") (class "Default")
      (node (ref "RN1") (pin "5") (pinfunction "5_5") (pintype "passive"))
      (node (ref "U15") (pin "5") (pinfunction "Y3_5") (pintype "tri_state"))
      (node (ref "U16") (pin "5") (pinfunction "Y3_5") (pintype "tri_state"))
      (node (ref "U17") (pin "5") (pinfunction "Y3_5") (pintype "tri_state"))
      (node (ref "U18") (pin "12") (pinfunction "E_12") (pintype "input"))
      (node (ref "U19") (pin "13") (pinfunction "C_13") (pintype "input"))
      (node (ref "U23") (pin "15") (pinfunction "B4_15") (pintype "bidirectional"))
      (node (ref "U24") (pin "5") (pinfunction "D3_5") (pintype "tri_state"))
      (node (ref "U25") (pin "5") (pinfunction "D3_5") (pintype "tri_state"))
    )
    (net (code "66") (name "D4") (class "Default")
      (node (ref "RN1") (pin "6") (pinfunction "6_6") (pintype "passive"))
      (node (ref "U15") (pin "14") (pinfunction "Y3_14") (pintype "tri_state"))
      (node (ref "U16") (pin "14") (pinfunction "Y3_14") (pintype "tri_state"))
      (node (ref "U17") (pin "14") (pinfunction "Y3_14") (pintype "tri_state"))
      (node (ref "U18") (pin "11") (pinfunction "D_11") (pintype "input"))
      (node (ref "U19") (pin "12") (pinfunction "B_12") (pintype "input"))
      (node (ref "U23") (pin "14") (pinfunction "B5_14") (pintype "bidirectional"))
      (node (ref "U24") (pin "6") (pinfunction "D4_6") (pintype "tri_state"))
      (node (ref "U25") (pin "6") (pinfunction "D4_6") (pintype "tri_state"))
    )
    (net (code "67") (name "D5") (class "Default")
      (node (ref "RN1") (pin "7") (pinfunction "7_7") (pintype "passive"))
      (node (ref "U15") (pin "7") (pinfunction "Y2_7") (pintype "tri_state"))
      (node (ref "U16") (pin "7") (pinfunction "Y2_7") (pintype "tri_state"))
      (node (ref "U17") (pin "7") (pinfunction "Y2_7") (pintype "tri_state"))
      (node (ref "U18") (pin "4") (pinfunction "I_4") (pintype "input"))
      (node (ref "U19") (pin "11") (pinfunction "A_11") (pintype "input"))
      (node (ref "U23") (pin "13") (pinfunction "B6_13") (pintype "bidirectional"))
      (node (ref "U24") (pin "7") (pinfunction "D5_7") (pintype "tri_state"))
      (node (ref "U25") (pin "7") (pinfunction "D5_7") (pintype "tri_state"))
    )
    (net (code "68") (name "D6") (class "Default")
      (node (ref "RN1") (pin "8") (pinfunction "8_8") (pintype "passive"))
      (node (ref "U15") (pin "12") (pinfunction "Y4_12") (pintype "tri_state"))
      (node (ref "U16") (pin "12") (pinfunction "Y4_12") (pintype "tri_state"))
      (node (ref "U17") (pin "12") (pinfunction "Y4_12") (pintype "tri_state"))
      (node (ref "U18") (pin "10") (pinfunction "C_10") (pintype "input"))
      (node (ref "U20") (pin "6") (pinfunction "H_6") (pintype "input"))
      (node (ref "U23") (pin "12") (pinfunction "B7_12") (pintype "bidirectional"))
      (node (ref "U24") (pin "8") (pinfunction "D6_8") (pintype "tri_state"))
      (node (ref "U25") (pin "8") (pinfunction "D6_8") (pintype "tri_state"))
    )
    (net (code "69") (name "D7") (class "Default")
      (node (ref "RN1") (pin "9") (pinfunction "9_9") (pintype "passive"))
      (node (ref "U15") (pin "9") (pinfunction "Y1_9") (pintype "tri_state"))
      (node (ref "U16") (pin "9") (pinfunction "Y1_9") (pintype "tri_state"))
      (node (ref "U17") (pin "9") (pinfunction "Y1_9") (pintype "tri_state"))
      (node (ref "U18") (pin "9") (pinfunction "B_9") (pintype "input"))
      (node (ref "U20") (pin "5") (pinfunction "G_5") (pintype "input"))
      (node (ref "U23") (pin "11") (pinfunction "B8_11") (pintype "bidirectional"))
      (node (ref "U24") (pin "9") (pinfunction "D7_9") (pintype "tri_state"))
      (node (ref "U25") (pin "9") (pinfunction "D7_9") (pintype "tri_state"))
    )
    (net (code "70") (name "GND") (class "Default")
      (node (ref "C1") (pin "P$2") (pinfunction "2_P$2") (pintype "passive"))
      (node (ref "C10") (pin "P$2") (pinfunction "2_P$2") (pintype "passive"))
      (node (ref "C11") (pin "P$2") (pinfunction "2_P$2") (pintype "passive"))
      (node (ref "C12") (pin "P$2") (pinfunction "2_P$2") (pintype "passive"))
      (node (ref "C13") (pin "P$2") (pinfunction "2_P$2") (pintype "passive"))
      (node (ref "C14") (pin "P$2") (pinfunction "2_P$2") (pintype "passive"))
      (node (ref "C15") (pin "P$2") (pinfunction "2_P$2") (pintype "passive"))
      (node (ref "C16") (pin "P$2") (pinfunction "2_P$2") (pintype "passive"))
      (node (ref "C17") (pin "P$2") (pinfunction "2_P$2") (pintype "passive"))
      (node (ref "C18") (pin "P$2") (pinfunction "2_P$2") (pintype "passive"))
      (node (ref "C19") (pin "P$2") (pinfunction "2_P$2") (pintype "passive"))
      (node (ref "C2") (pin "P$2") (pinfunction "2_P$2") (pintype "passive"))
      (node (ref "C20") (pin "P$2") (pinfunction "2_P$2") (pintype "passive"))
      (node (ref "C21") (pin "P$2") (pinfunction "2_P$2") (pintype "passive"))
      (node (ref "C22") (pin "P$2") (pinfunction "2_P$2") (pintype "passive"))
      (node (ref "C23") (pin "P$2") (pinfunction "2_P$2") (pintype "passive"))
      (node (ref "C24") (pin "P$2") (pinfunction "2_P$2") (pintype "passive"))
      (node (ref "C25") (pin "P$2") (pinfunction "2_P$2") (pintype "passive"))
      (node (ref "C26") (pin "P$2") (pinfunction "2_P$2") (pintype "passive"))
      (node (ref "C27") (pin "P$2") (pinfunction "2_P$2") (pintype "passive"))
      (node (ref "C28") (pin "P$2") (pinfunction "2_P$2") (pintype "passive"))
      (node (ref "C29") (pin "P$2") (pinfunction "2_P$2") (pintype "passive"))
      (node (ref "C3") (pin "P$2") (pinfunction "2_P$2") (pintype "passive"))
      (node (ref "C30") (pin "-") (pinfunction "-_-") (pintype "passive"))
      (node (ref "C31") (pin "-") (pinfunction "-_-") (pintype "passive"))
      (node (ref "C32") (pin "P$2") (pinfunction "2_P$2") (pintype "passive"))
      (node (ref "C33") (pin "P$2") (pinfunction "2_P$2") (pintype "passive"))
      (node (ref "C34") (pin "-") (pinfunction "-_-") (pintype "passive"))
      (node (ref "C39") (pin "+") (pinfunction "+_+") (pintype "passive"))
      (node (ref "C4") (pin "P$2") (pinfunction "2_P$2") (pintype "passive"))
      (node (ref "C40") (pin "P$2") (pinfunction "2_P$2") (pintype "passive"))
      (node (ref "C5") (pin "P$2") (pinfunction "2_P$2") (pintype "passive"))
      (node (ref "C6") (pin "P$2") (pinfunction "2_P$2") (pintype "passive"))
      (node (ref "C7") (pin "P$2") (pinfunction "2_P$2") (pintype "passive"))
      (node (ref "C8") (pin "P$2") (pinfunction "2_P$2") (pintype "passive"))
      (node (ref "C9") (pin "P$2") (pinfunction "2_P$2") (pintype "passive"))
      (node (ref "CE0") (pin "3") (pinfunction "GND_3") (pintype "bidirectional"))
      (node (ref "CE0") (pin "4") (pinfunction "GND_4") (pintype "bidirectional"))
      (node (ref "CE0") (pin "62") (pinfunction "GND_62") (pintype "bidirectional"))
      (node (ref "J1") (pin "P$5") (pinfunction "P$5_P$5") (pintype "bidirectional"))
      (node (ref "J2") (pin "P$5") (pinfunction "P$5_P$5") (pintype "bidirectional"))
      (node (ref "J3") (pin "3") (pinfunction "3_3") (pintype "bidirectional"))
      (node (ref "J4") (pin "3") (pinfunction "3_3") (pintype "passive"))
      (node (ref "J5") (pin "3") (pinfunction "3_3") (pintype "passive"))
      (node (ref "JP4") (pin "1") (pinfunction "1_1") (pintype "passive"))
      (node (ref "JP5") (pin "1") (pinfunction "1_1") (pintype "passive"))
      (node (ref "JP6") (pin "1") (pinfunction "1_1") (pintype "passive"))
      (node (ref "JP7") (pin "1") (pinfunction "1_1") (pintype "passive"))
      (node (ref "Q1") (pin "1") (pinfunction "E_1") (pintype "passive"))
      (node (ref "Q2") (pin "1") (pinfunction "E_1") (pintype "passive"))
      (node (ref "Q3") (pin "1") (pinfunction "E_1") (pintype "passive"))
      (node (ref "R8") (pin "1") (pinfunction "1_1") (pintype "passive"))
      (node (ref "R9") (pin "1") (pinfunction "1_1") (pintype "passive"))
      (node (ref "U1") (pin "1") (pinfunction "GND_1") (pintype "power_in"))
      (node (ref "U10") (pin "1") (pinfunction "G_1") (pintype "input"))
      (node (ref "U16") (pin "17") (pinfunction "A4_17") (pintype "input"))
      (node (ref "U16") (pin "2") (pinfunction "A1_2") (pintype "input"))
      (node (ref "U16") (pin "4") (pinfunction "A2_4") (pintype "input"))
      (node (ref "U18") (pin "8") (pinfunction "A_8") (pintype "input"))
      (node (ref "U19") (pin "5") (pinfunction "G_5") (pintype "input"))
      (node (ref "U19") (pin "6") (pinfunction "H_6") (pintype "input"))
      (node (ref "U21") (pin "1") (pinfunction "G_1") (pintype "input"))
      (node (ref "U21") (pin "19") (pinfunction "G_19") (pintype "input"))
      (node (ref "U24") (pin "21") (pinfunction "IOW_21") (pintype "input"))
      (node (ref "U24") (pin "25") (pinfunction "IOR_25") (pintype "input"))
      (node (ref "U24") (pin "28") (pinfunction "~{AS}_28") (pintype "input"))
      (node (ref "U25") (pin "21") (pinfunction "IOW_21") (pintype "input"))
      (node (ref "U25") (pin "25") (pinfunction "IOR_25") (pintype "input"))
      (node (ref "U25") (pin "28") (pinfunction "~{AS}_28") (pintype "input"))
      (node (ref "U26") (pin "11") (pinfunction "GND_11") (pintype "power_in"))
      (node (ref "U27") (pin "11") (pinfunction "GND_11") (pintype "power_in"))
      (node (ref "U29") (pin "3") (pinfunction "GND_3") (pintype "input"))
      (node (ref "U8") (pin "8") (pinfunction "GND_8") (pintype "power_in"))
      (node (ref "Y1") (pin "4") (pinfunction "GND_4") (pintype "power_in"))
    )
    (net (code "71") (name "ID0") (class "Default")
      (node (ref "U15") (pin "2") (pinfunction "A1_2") (pintype "input"))
    )
    (net (code "72") (name "ID1") (class "Default")
      (node (ref "U15") (pin "17") (pinfunction "A4_17") (pintype "input"))
    )
    (net (code "73") (name "ID2") (class "Default")
      (node (ref "U15") (pin "4") (pinfunction "A2_4") (pintype "input"))
    )
    (net (code "74") (name "ID3") (class "Default")
      (node (ref "U15") (pin "15") (pinfunction "A3_15") (pintype "input"))
    )
    (net (code "75") (name "ID4") (class "Default")
      (node (ref "U15") (pin "6") (pinfunction "A3_6") (pintype "input"))
    )
    (net (code "76") (name "ID5") (class "Default")
      (node (ref "U15") (pin "13") (pinfunction "A2_13") (pintype "input"))
    )
    (net (code "77") (name "ID6") (class "Default")
      (node (ref "U15") (pin "8") (pinfunction "A4_8") (pintype "input"))
    )
    (net (code "78") (name "ID7") (class "Default")
      (node (ref "U15") (pin "11") (pinfunction "A1_11") (pintype "input"))
    )
    (net (code "79") (name "INT_KB") (class "Default")
      (node (ref "R3") (pin "1") (pinfunction "1_1") (pintype "passive"))
      (node (ref "U14") (pin "1") (pinfunction "CLR_1") (pintype "input"))
      (node (ref "U14") (pin "9") (pinfunction "Q_9") (pintype "output"))
      (node (ref "U16") (pin "13") (pinfunction "A2_13") (pintype "input"))
    )
    (net (code "80") (name "INT_UART1") (class "Default")
      (node (ref "JP1") (pin "1") (pinfunction "1_1") (pintype "passive"))
      (node (ref "U16") (pin "11") (pinfunction "A1_11") (pintype "input"))
      (node (ref "U24") (pin "33") (pinfunction "INT_33") (pintype "output"))
    )
    (net (code "81") (name "INT_UART2") (class "Default")
      (node (ref "JP2") (pin "1") (pinfunction "1_1") (pintype "passive"))
      (node (ref "U16") (pin "8") (pinfunction "A4_8") (pintype "input"))
      (node (ref "U25") (pin "33") (pinfunction "INT_33") (pintype "output"))
    )
    (net (code "82") (name "KB_CLOCK") (class "Default")
      (node (ref "J3") (pin "5") (pinfunction "5_5") (pintype "bidirectional"))
      (node (ref "Q1") (pin "3") (pinfunction "C_3") (pintype "passive"))
      (node (ref "Q2") (pin "3") (pinfunction "C_3") (pintype "passive"))
      (node (ref "R1") (pin "1") (pinfunction "1_1") (pintype "passive"))
      (node (ref "TP1") (pin "1") (pinfunction "1_1") (pintype "passive"))
      (node (ref "U28") (pin "11") (pinfunction "I_11") (pintype "input"))
    )
    (net (code "83") (name "KB_DATA") (class "Default")
      (node (ref "J3") (pin "1") (pinfunction "1_1") (pintype "bidirectional"))
      (node (ref "Q3") (pin "3") (pinfunction "C_3") (pintype "passive"))
      (node (ref "R6") (pin "1") (pinfunction "1_1") (pintype "passive"))
      (node (ref "TP2") (pin "1") (pinfunction "1_1") (pintype "passive"))
      (node (ref "U28") (pin "13") (pinfunction "I_13") (pintype "input"))
    )
    (net (code "84") (name "KB_ERR") (class "Default")
      (node (ref "U16") (pin "6") (pinfunction "A3_6") (pintype "input"))
      (node (ref "U2") (pin "3") (pinfunction "O_3") (pintype "output"))
    )
    (net (code "85") (name "KB_WRCYCLE") (class "Default")
      (node (ref "U16") (pin "15") (pinfunction "A3_15") (pintype "input"))
      (node (ref "U3") (pin "10") (pinfunction "I1_10") (pintype "input"))
      (node (ref "U5") (pin "5") (pinfunction "Q_5") (pintype "output"))
      (node (ref "U6") (pin "11") (pinfunction "CLK_11") (pintype "input"))
      (node (ref "U7") (pin "10") (pinfunction "I1_10") (pintype "input"))
    )
    (net (code "86") (name "Net-(C29-1)") (class "Default")
      (node (ref "C29") (pin "P$1") (pinfunction "1_P$1") (pintype "passive"))
      (node (ref "U1") (pin "5") (pinfunction "CON_5") (pintype "input"))
    )
    (net (code "87") (name "Net-(CE0-D0)") (class "Default")
      (node (ref "CE0") (pin "43") (pinfunction "D0_43") (pintype "bidirectional"))
      (node (ref "U23") (pin "2") (pinfunction "A1_2") (pintype "bidirectional"))
    )
    (net (code "88") (name "Net-(CE0-D1)") (class "Default")
      (node (ref "CE0") (pin "44") (pinfunction "D1_44") (pintype "bidirectional"))
      (node (ref "U23") (pin "3") (pinfunction "A2_3") (pintype "bidirectional"))
    )
    (net (code "89") (name "Net-(CE0-D2)") (class "Default")
      (node (ref "CE0") (pin "45") (pinfunction "D2_45") (pintype "bidirectional"))
      (node (ref "U23") (pin "4") (pinfunction "A3_4") (pintype "bidirectional"))
    )
    (net (code "90") (name "Net-(CE0-D3)") (class "Default")
      (node (ref "CE0") (pin "46") (pinfunction "D3_46") (pintype "bidirectional"))
      (node (ref "U23") (pin "5") (pinfunction "A4_5") (pintype "bidirectional"))
    )
    (net (code "91") (name "Net-(CE0-D4)") (class "Default")
      (node (ref "CE0") (pin "47") (pinfunction "D4_47") (pintype "bidirectional"))
      (node (ref "U23") (pin "6") (pinfunction "A5_6") (pintype "bidirectional"))
    )
    (net (code "92") (name "Net-(CE0-D5)") (class "Default")
      (node (ref "CE0") (pin "48") (pinfunction "D5_48") (pintype "bidirectional"))
      (node (ref "U23") (pin "7") (pinfunction "A6_7") (pintype "bidirectional"))
    )
    (net (code "93") (name "Net-(CE0-D6)") (class "Default")
      (node (ref "CE0") (pin "49") (pinfunction "D6_49") (pintype "bidirectional"))
      (node (ref "U23") (pin "8") (pinfunction "A7_8") (pintype "bidirectional"))
    )
    (net (code "94") (name "Net-(CE0-D7)") (class "Default")
      (node (ref "CE0") (pin "50") (pinfunction "D7_50") (pintype "bidirectional"))
      (node (ref "U23") (pin "9") (pinfunction "A8_9") (pintype "bidirectional"))
    )
    (net (code "95") (name "Net-(Q1-B)") (class "Default")
      (node (ref "Q1") (pin "2") (pinfunction "B_2") (pintype "passive"))
      (node (ref "R2") (pin "2") (pinfunction "2_2") (pintype "passive"))
    )
    (net (code "96") (name "Net-(Q2-B)") (class "Default")
      (node (ref "Q2") (pin "2") (pinfunction "B_2") (pintype "passive"))
      (node (ref "R3") (pin "2") (pinfunction "2_2") (pintype "passive"))
    )
    (net (code "97") (name "Net-(Q3-B)") (class "Default")
      (node (ref "Q3") (pin "2") (pinfunction "B_2") (pintype "passive"))
      (node (ref "R5") (pin "2") (pinfunction "2_2") (pintype "passive"))
    )
    (net (code "98") (name "Net-(U1-DIS)") (class "Default")
      (node (ref "C30") (pin "+") (pinfunction "+_+") (pintype "passive"))
      (node (ref "R7") (pin "2") (pinfunction "2_2") (pintype "passive"))
      (node (ref "U1") (pin "6") (pinfunction "TRE_6") (pintype "input"))
      (node (ref "U1") (pin "7") (pinfunction "DIS_7") (pintype "input"))
    )
    (net (code "99") (name "Net-(U1-OUT)") (class "Default")
      (node (ref "R2") (pin "1") (pinfunction "1_1") (pintype "passive"))
      (node (ref "U1") (pin "3") (pinfunction "OUT_3") (pintype "output"))
      (node (ref "U4") (pin "13") (pinfunction "I_13") (pintype "input"))
    )
    (net (code "100") (name "Net-(U1-TRI)") (class "Default")
      (node (ref "U1") (pin "2") (pinfunction "TRI_2") (pintype "input"))
      (node (ref "U6") (pin "8") (pinfunction "~{Q}_8") (pintype "output"))
    )
    (net (code "101") (name "Net-(U2A-I0)") (class "Default")
      (node (ref "U2") (pin "1") (pinfunction "I0_1") (pintype "input"))
      (node (ref "U6") (pin "5") (pinfunction "Q_5") (pintype "output"))
    )
    (net (code "102") (name "Net-(U3A-I2)") (class "Default")
      (node (ref "JP3") (pin "2") (pinfunction "2_2") (pintype "passive"))
      (node (ref "R4") (pin "1") (pinfunction "1_1") (pintype "passive"))
      (node (ref "U3") (pin "13") (pinfunction "I2_13") (pintype "input"))
    )
    (net (code "103") (name "Net-(U3B-I1)") (class "Default")
      (node (ref "U3") (pin "4") (pinfunction "I1_4") (pintype "input"))
      (node (ref "U4") (pin "4") (pinfunction "O_4") (pintype "output"))
      (node (ref "U7") (pin "2") (pinfunction "I1_2") (pintype "input"))
    )
    (net (code "104") (name "Net-(U3B-I2)") (class "Default")
      (node (ref "U3") (pin "5") (pinfunction "I2_5") (pintype "input"))
      (node (ref "U4") (pin "10") (pinfunction "O_10") (pintype "output"))
    )
    (net (code "105") (name "Net-(U3B-O)") (class "Default")
      (node (ref "U3") (pin "6") (pinfunction "O_6") (pintype "output"))
      (node (ref "U4") (pin "5") (pinfunction "I_5") (pintype "input"))
    )
    (net (code "106") (name "Net-(U3C-O)") (class "Default")
      (node (ref "U3") (pin "8") (pinfunction "O_8") (pintype "output"))
      (node (ref "U5") (pin "12") (pinfunction "D_12") (pintype "input"))
    )
    (net (code "107") (name "Net-(U4F-O)") (class "Default")
      (node (ref "U4") (pin "12") (pinfunction "O_12") (pintype "output"))
      (node (ref "U6") (pin "13") (pinfunction "CLR_13") (pintype "input"))
    )
    (net (code "108") (name "Net-(U5A-CLR)") (class "Default")
      (node (ref "U5") (pin "1") (pinfunction "CLR_1") (pintype "input"))
      (node (ref "U5") (pin "9") (pinfunction "Q_9") (pintype "output"))
    )
    (net (code "109") (name "Net-(U7C-O)") (class "Default")
      (node (ref "R5") (pin "1") (pinfunction "1_1") (pintype "passive"))
      (node (ref "U7") (pin "8") (pinfunction "O_8") (pintype "output"))
    )
    (net (code "110") (name "Net-(U10A-A)") (class "Default")
      (node (ref "U10") (pin "8") (pinfunction "A_8") (pintype "input"))
      (node (ref "U11") (pin "9") (pinfunction "Q4_9") (pintype "output"))
      (node (ref "U17") (pin "6") (pinfunction "A3_6") (pintype "input"))
    )
    (net (code "111") (name "Net-(U10A-B)") (class "Default")
      (node (ref "U10") (pin "9") (pinfunction "B_9") (pintype "input"))
      (node (ref "U11") (pin "12") (pinfunction "Q5_12") (pintype "output"))
      (node (ref "U17") (pin "15") (pinfunction "A3_15") (pintype "input"))
    )
    (net (code "112") (name "Net-(U10A-C)") (class "Default")
      (node (ref "U10") (pin "10") (pinfunction "C_10") (pintype "input"))
      (node (ref "U11") (pin "15") (pinfunction "Q6_15") (pintype "output"))
      (node (ref "U17") (pin "4") (pinfunction "A2_4") (pintype "input"))
    )
    (net (code "113") (name "Net-(U10A-D)") (class "Default")
      (node (ref "U10") (pin "11") (pinfunction "D_11") (pintype "input"))
      (node (ref "U11") (pin "6") (pinfunction "Q3_6") (pintype "output"))
      (node (ref "U17") (pin "13") (pinfunction "A2_13") (pintype "input"))
    )
    (net (code "114") (name "Net-(U10A-E)") (class "Default")
      (node (ref "U10") (pin "12") (pinfunction "E_12") (pintype "input"))
      (node (ref "U11") (pin "5") (pinfunction "Q2_5") (pintype "output"))
      (node (ref "U17") (pin "8") (pinfunction "A4_8") (pintype "input"))
    )
    (net (code "115") (name "Net-(U10A-F)") (class "Default")
      (node (ref "U10") (pin "13") (pinfunction "F_13") (pintype "input"))
      (node (ref "U11") (pin "19") (pinfunction "Q8_19") (pintype "output"))
      (node (ref "U17") (pin "2") (pinfunction "A1_2") (pintype "input"))
    )
    (net (code "116") (name "Net-(U10A-H)") (class "Default")
      (node (ref "U10") (pin "2") (pinfunction "H_2") (pintype "input"))
      (node (ref "U11") (pin "2") (pinfunction "Q1_2") (pintype "output"))
      (node (ref "U17") (pin "11") (pinfunction "A1_11") (pintype "input"))
    )
    (net (code "117") (name "Net-(U10A-I)") (class "Default")
      (node (ref "U10") (pin "4") (pinfunction "I_4") (pintype "input"))
      (node (ref "U11") (pin "16") (pinfunction "Q7_16") (pintype "output"))
      (node (ref "U17") (pin "17") (pinfunction "A4_17") (pintype "input"))
    )
    (net (code "118") (name "Net-(U10A-SOD)") (class "Default")
      (node (ref "U10") (pin "6") (pinfunction "SOD_6") (pintype "output"))
      (node (ref "U2") (pin "2") (pinfunction "I1_2") (pintype "input"))
    )
    (net (code "119") (name "Net-(U11A-CLK)") (class "Default")
      (node (ref "U11") (pin "11") (pinfunction "CLK_11") (pintype "input"))
      (node (ref "U4") (pin "6") (pinfunction "O_6") (pintype "output"))
      (node (ref "U4") (pin "9") (pinfunction "I_9") (pintype "input"))
      (node (ref "U6") (pin "3") (pinfunction "CLK_3") (pintype "input"))
    )
    (net (code "120") (name "Net-(U11A-D1)") (class "Default")
      (node (ref "U11") (pin "3") (pinfunction "D1_3") (pintype "input"))
      (node (ref "U12") (pin "4") (pinfunction "QB_4") (pintype "output"))
    )
    (net (code "121") (name "Net-(U11A-D2)") (class "Default")
      (node (ref "U11") (pin "4") (pinfunction "D2_4") (pintype "input"))
      (node (ref "U12") (pin "5") (pinfunction "QC_5") (pintype "output"))
    )
    (net (code "122") (name "Net-(U11A-D3)") (class "Default")
      (node (ref "U11") (pin "7") (pinfunction "D3_7") (pintype "input"))
      (node (ref "U12") (pin "6") (pinfunction "QD_6") (pintype "output"))
    )
    (net (code "123") (name "Net-(U11A-D4)") (class "Default")
      (node (ref "U11") (pin "8") (pinfunction "D4_8") (pintype "input"))
      (node (ref "U12") (pin "10") (pinfunction "QE_10") (pintype "output"))
    )
    (net (code "124") (name "Net-(U11A-D5)") (class "Default")
      (node (ref "U11") (pin "13") (pinfunction "D5_13") (pintype "input"))
      (node (ref "U12") (pin "11") (pinfunction "QF_11") (pintype "output"))
    )
    (net (code "125") (name "Net-(U11A-D6)") (class "Default")
      (node (ref "U11") (pin "14") (pinfunction "D6_14") (pintype "input"))
      (node (ref "U12") (pin "12") (pinfunction "QG_12") (pintype "output"))
    )
    (net (code "126") (name "Net-(U11A-D7)") (class "Default")
      (node (ref "U11") (pin "17") (pinfunction "D7_17") (pintype "input"))
      (node (ref "U12") (pin "13") (pinfunction "QH_13") (pintype "output"))
      (node (ref "U13") (pin "1") (pinfunction "A_1") (pintype "input"))
    )
    (net (code "127") (name "Net-(U11A-D8)") (class "Default")
      (node (ref "U11") (pin "18") (pinfunction "D8_18") (pintype "input"))
      (node (ref "U13") (pin "3") (pinfunction "QA_3") (pintype "output"))
    )
    (net (code "128") (name "Net-(U12A-CLR)") (class "Default")
      (node (ref "U12") (pin "9") (pinfunction "CLR_9") (pintype "input"))
      (node (ref "U13") (pin "9") (pinfunction "CLR_9") (pintype "input"))
      (node (ref "U7") (pin "3") (pinfunction "O_3") (pintype "output"))
    )
    (net (code "129") (name "Net-(U12A-QA)") (class "Default")
      (node (ref "U12") (pin "3") (pinfunction "QA_3") (pintype "output"))
      (node (ref "U6") (pin "2") (pinfunction "D_2") (pintype "input"))
    )
    (net (code "130") (name "Net-(U13A-QB)") (class "Default")
      (node (ref "U13") (pin "4") (pinfunction "QB_4") (pintype "output"))
      (node (ref "U3") (pin "3") (pinfunction "I0_3") (pintype "input"))
    )
    (net (code "131") (name "Net-(U13A-QC)") (class "Default")
      (node (ref "U13") (pin "5") (pinfunction "QC_5") (pintype "output"))
      (node (ref "U4") (pin "3") (pinfunction "I_3") (pintype "input"))
    )
    (net (code "132") (name "Net-(U14A-~{Q})") (class "Default")
      (node (ref "U14") (pin "6") (pinfunction "~{Q}_6") (pintype "output"))
      (node (ref "U7") (pin "5") (pinfunction "I1_5") (pintype "input"))
    )
    (net (code "133") (name "Net-(U14B-CLK)") (class "Default")
      (node (ref "U14") (pin "11") (pinfunction "CLK_11") (pintype "input"))
      (node (ref "U4") (pin "8") (pinfunction "O_8") (pintype "output"))
    )
    (net (code "134") (name "Net-(U14B-CLR)") (class "Default")
      (node (ref "U14") (pin "13") (pinfunction "CLR_13") (pintype "input"))
      (node (ref "U7") (pin "6") (pinfunction "O_6") (pintype "output"))
    )
    (net (code "135") (name "Net-(U15A-G)") (class "Default")
      (node (ref "U15") (pin "1") (pinfunction "G_1") (pintype "input"))
      (node (ref "U15") (pin "19") (pinfunction "G_19") (pintype "input"))
      (node (ref "U9") (pin "7") (pinfunction "Y7_7") (pintype "output"))
    )
    (net (code "136") (name "Net-(U16A-G)") (class "Default")
      (node (ref "U16") (pin "1") (pinfunction "G_1") (pintype "input"))
      (node (ref "U16") (pin "19") (pinfunction "G_19") (pintype "input"))
      (node (ref "U9") (pin "14") (pinfunction "Y1_14") (pintype "output"))
    )
    (net (code "137") (name "Net-(U18A-SEV)") (class "Default")
      (node (ref "U18") (pin "5") (pinfunction "SEV_5") (pintype "output"))
      (node (ref "U20") (pin "4") (pinfunction "F_4") (pintype "input"))
    )
    (net (code "138") (name "Net-(U19A-QH)") (class "Default")
      (node (ref "U19") (pin "9") (pinfunction "QH_9") (pintype "output"))
      (node (ref "U3") (pin "11") (pinfunction "I2_11") (pintype "input"))
    )
    (net (code "139") (name "Net-(U19A-SER)") (class "Default")
      (node (ref "U19") (pin "10") (pinfunction "SER_10") (pintype "input"))
      (node (ref "U20") (pin "9") (pinfunction "QH_9") (pintype "output"))
    )
    (net (code "140") (name "Net-(U19A-~{QH})") (class "Default")
      (node (ref "U19") (pin "7") (pinfunction "~{QH}_7") (pintype "output"))
      (node (ref "U7") (pin "9") (pinfunction "I0_9") (pintype "input"))
    )
    (net (code "141") (name "Net-(U22A-O)") (class "Default")
      (node (ref "U22") (pin "2") (pinfunction "O_2") (pintype "output"))
      (node (ref "U24") (pin "14") (pinfunction "CS0_14") (pintype "input"))
    )
    (net (code "142") (name "Net-(U22B-O)") (class "Default")
      (node (ref "U22") (pin "4") (pinfunction "O_4") (pintype "output"))
      (node (ref "U24") (pin "15") (pinfunction "CS1_15") (pintype "input"))
      (node (ref "U25") (pin "15") (pinfunction "CS1_15") (pintype "input"))
    )
    (net (code "143") (name "Net-(U22D-I)") (class "Default")
      (node (ref "JP1") (pin "2") (pinfunction "2_2") (pintype "passive"))
      (node (ref "R8") (pin "2") (pinfunction "2_2") (pintype "passive"))
      (node (ref "U22") (pin "9") (pinfunction "I_9") (pintype "input"))
    )
    (net (code "144") (name "Net-(U22D-O)") (class "Default")
      (node (ref "U22") (pin "8") (pinfunction "O_8") (pintype "output"))
      (node (ref "U3") (pin "1") (pinfunction "I0_1") (pintype "input"))
    )
    (net (code "145") (name "Net-(U22E-I)") (class "Default")
      (node (ref "JP2") (pin "2") (pinfunction "2_2") (pintype "passive"))
      (node (ref "R9") (pin "2") (pinfunction "2_2") (pintype "passive"))
      (node (ref "U22") (pin "11") (pinfunction "I_11") (pintype "input"))
    )
    (net (code "146") (name "Net-(U22E-O)") (class "Default")
      (node (ref "U22") (pin "10") (pinfunction "O_10") (pintype "output"))
      (node (ref "U3") (pin "2") (pinfunction "I1_2") (pintype "input"))
    )
    (net (code "147") (name "Net-(U22F-I)") (class "Default")
      (node (ref "U22") (pin "13") (pinfunction "I_13") (pintype "input"))
      (node (ref "U3") (pin "12") (pinfunction "O_12") (pintype "output"))
    )
    (net (code "148") (name "Net-(U24A-RCLK)") (class "Default")
      (node (ref "U24") (pin "10") (pinfunction "RCLK_10") (pintype "input"))
      (node (ref "U24") (pin "17") (pinfunction "~{BAUDOUT}_17") (pintype "output"))
    )
    (net (code "149") (name "Net-(U24A-RX)") (class "Default")
      (node (ref "U24") (pin "11") (pinfunction "RX_11") (pintype "input"))
      (node (ref "U26") (pin "17") (pinfunction "RY3_17") (pintype "output"))
    )
    (net (code "150") (name "Net-(U24A-TX)") (class "Default")
      (node (ref "U24") (pin "13") (pinfunction "TX_13") (pintype "output"))
      (node (ref "U26") (pin "15") (pinfunction "DA2_15") (pintype "input"))
    )
    (net (code "151") (name "Net-(U24A-XTAL1)") (class "Default")
      (node (ref "U24") (pin "18") (pinfunction "XTAL1_18") (pintype "input"))
      (node (ref "U25") (pin "18") (pinfunction "XTAL1_18") (pintype "input"))
      (node (ref "Y1") (pin "5") (pinfunction "FO_5") (pintype "output"))
    )
    (net (code "152") (name "Net-(U24A-~{CD})") (class "Default")
      (node (ref "U24") (pin "42") (pinfunction "~{CD}_42") (pintype "input"))
      (node (ref "U26") (pin "19") (pinfunction "RY1_19") (pintype "output"))
    )
    (net (code "153") (name "Net-(U24A-~{CTS})") (class "Default")
      (node (ref "U24") (pin "40") (pinfunction "~{CTS}_40") (pintype "input"))
      (node (ref "U26") (pin "14") (pinfunction "RY4_14") (pintype "output"))
    )
    (net (code "154") (name "Net-(U24A-~{DSR})") (class "Default")
      (node (ref "U24") (pin "41") (pinfunction "~{DSR}_41") (pintype "input"))
      (node (ref "U26") (pin "18") (pinfunction "RY2_18") (pintype "output"))
    )
    (net (code "155") (name "Net-(U24A-~{DTR})") (class "Default")
      (node (ref "U24") (pin "37") (pinfunction "~{DTR}_37") (pintype "output"))
      (node (ref "U26") (pin "13") (pinfunction "DA3_13") (pintype "input"))
    )
    (net (code "156") (name "Net-(U24A-~{OP1})") (class "Default")
      (node (ref "J4") (pin "1") (pinfunction "1_1") (pintype "passive"))
      (node (ref "U24") (pin "38") (pinfunction "~{OP1}_38") (pintype "output"))
    )
    (net (code "157") (name "Net-(U24A-~{OP2})") (class "Default")
      (node (ref "J4") (pin "2") (pinfunction "2_2") (pintype "passive"))
      (node (ref "U24") (pin "35") (pinfunction "~{OP2}_35") (pintype "output"))
    )
    (net (code "158") (name "Net-(U24A-~{RI})") (class "Default")
      (node (ref "U24") (pin "43") (pinfunction "~{RI}_43") (pintype "input"))
      (node (ref "U26") (pin "12") (pinfunction "RY5_12") (pintype "output"))
    )
    (net (code "159") (name "Net-(U24A-~{RTS})") (class "Default")
      (node (ref "U24") (pin "36") (pinfunction "~{RTS}_36") (pintype "output"))
      (node (ref "U26") (pin "16") (pinfunction "DA1_16") (pintype "input"))
    )
    (net (code "160") (name "Net-(U25A-RCLK)") (class "Default")
      (node (ref "U25") (pin "10") (pinfunction "RCLK_10") (pintype "input"))
      (node (ref "U25") (pin "17") (pinfunction "~{BAUDOUT}_17") (pintype "output"))
    )
    (net (code "161") (name "Net-(U25A-RX)") (class "Default")
      (node (ref "U25") (pin "11") (pinfunction "RX_11") (pintype "input"))
      (node (ref "U27") (pin "17") (pinfunction "RY3_17") (pintype "output"))
    )
    (net (code "162") (name "Net-(U25A-TX)") (class "Default")
      (node (ref "U25") (pin "13") (pinfunction "TX_13") (pintype "output"))
      (node (ref "U27") (pin "15") (pinfunction "DA2_15") (pintype "input"))
    )
    (net (code "163") (name "Net-(U25A-~{CD})") (class "Default")
      (node (ref "U25") (pin "42") (pinfunction "~{CD}_42") (pintype "input"))
      (node (ref "U27") (pin "19") (pinfunction "RY1_19") (pintype "output"))
    )
    (net (code "164") (name "Net-(U25A-~{CTS})") (class "Default")
      (node (ref "U25") (pin "40") (pinfunction "~{CTS}_40") (pintype "input"))
      (node (ref "U27") (pin "14") (pinfunction "RY4_14") (pintype "output"))
    )
    (net (code "165") (name "Net-(U25A-~{DSR})") (class "Default")
      (node (ref "U25") (pin "41") (pinfunction "~{DSR}_41") (pintype "input"))
      (node (ref "U27") (pin "18") (pinfunction "RY2_18") (pintype "output"))
    )
    (net (code "166") (name "Net-(U25A-~{DTR})") (class "Default")
      (node (ref "U25") (pin "37") (pinfunction "~{DTR}_37") (pintype "output"))
      (node (ref "U27") (pin "13") (pinfunction "DA3_13") (pintype "input"))
    )
    (net (code "167") (name "Net-(U25A-~{OP1})") (class "Default")
      (node (ref "J5") (pin "1") (pinfunction "1_1") (pintype "passive"))
      (node (ref "U25") (pin "38") (pinfunction "~{OP1}_38") (pintype "output"))
    )
    (net (code "168") (name "Net-(U25A-~{OP2})") (class "Default")
      (node (ref "J5") (pin "2") (pinfunction "2_2") (pintype "passive"))
      (node (ref "U25") (pin "35") (pinfunction "~{OP2}_35") (pintype "output"))
    )
    (net (code "169") (name "Net-(U25A-~{RI})") (class "Default")
      (node (ref "U25") (pin "43") (pinfunction "~{RI}_43") (pintype "input"))
      (node (ref "U27") (pin "12") (pinfunction "RY5_12") (pintype "output"))
    )
    (net (code "170") (name "Net-(U25A-~{RTS})") (class "Default")
      (node (ref "U25") (pin "36") (pinfunction "~{RTS}_36") (pintype "output"))
      (node (ref "U27") (pin "16") (pinfunction "DA1_16") (pintype "input"))
    )
    (net (code "171") (name "Net-(U26-DY1)") (class "Default")
      (node (ref "J1") (pin "P$7") (pinfunction "P$7_P$7") (pintype "bidirectional"))
      (node (ref "U26") (pin "5") (pinfunction "DY1_5") (pintype "output"))
    )
    (net (code "172") (name "Net-(U26-DY2)") (class "Default")
      (node (ref "J1") (pin "P$3") (pinfunction "P$3_P$3") (pintype "bidirectional"))
      (node (ref "U26") (pin "6") (pinfunction "DY2_6") (pintype "output"))
    )
    (net (code "173") (name "Net-(U26-DY3)") (class "Default")
      (node (ref "J1") (pin "P$4") (pinfunction "P$4_P$4") (pintype "bidirectional"))
      (node (ref "U26") (pin "8") (pinfunction "DY3_8") (pintype "output"))
    )
    (net (code "174") (name "Net-(U26-RA1)") (class "Default")
      (node (ref "J1") (pin "P$1") (pinfunction "P$1_P$1") (pintype "bidirectional"))
      (node (ref "U26") (pin "2") (pinfunction "RA1_2") (pintype "input"))
    )
    (net (code "175") (name "Net-(U26-RA2)") (class "Default")
      (node (ref "J1") (pin "P$6") (pinfunction "P$6_P$6") (pintype "bidirectional"))
      (node (ref "U26") (pin "3") (pinfunction "RA2_3") (pintype "input"))
    )
    (net (code "176") (name "Net-(U26-RA3)") (class "Default")
      (node (ref "J1") (pin "P$2") (pinfunction "P$2_P$2") (pintype "bidirectional"))
      (node (ref "U26") (pin "4") (pinfunction "RA3_4") (pintype "input"))
    )
    (net (code "177") (name "Net-(U26-RA4)") (class "Default")
      (node (ref "J1") (pin "P$8") (pinfunction "P$8_P$8") (pintype "bidirectional"))
      (node (ref "U26") (pin "7") (pinfunction "RA4_7") (pintype "input"))
    )
    (net (code "178") (name "Net-(U26-RA5)") (class "Default")
      (node (ref "J1") (pin "P$9") (pinfunction "P$9_P$9") (pintype "bidirectional"))
      (node (ref "U26") (pin "9") (pinfunction "RA5_9") (pintype "input"))
    )
    (net (code "179") (name "Net-(U27-DY1)") (class "Default")
      (node (ref "J2") (pin "P$7") (pinfunction "P$7_P$7") (pintype "bidirectional"))
      (node (ref "U27") (pin "5") (pinfunction "DY1_5") (pintype "output"))
    )
    (net (code "180") (name "Net-(U27-DY2)") (class "Default")
      (node (ref "J2") (pin "P$3") (pinfunction "P$3_P$3") (pintype "bidirectional"))
      (node (ref "U27") (pin "6") (pinfunction "DY2_6") (pintype "output"))
    )
    (net (code "181") (name "Net-(U27-DY3)") (class "Default")
      (node (ref "J2") (pin "P$4") (pinfunction "P$4_P$4") (pintype "bidirectional"))
      (node (ref "U27") (pin "8") (pinfunction "DY3_8") (pintype "output"))
    )
    (net (code "182") (name "Net-(U27-RA1)") (class "Default")
      (node (ref "J2") (pin "P$1") (pinfunction "P$1_P$1") (pintype "bidirectional"))
      (node (ref "U27") (pin "2") (pinfunction "RA1_2") (pintype "input"))
    )
    (net (code "183") (name "Net-(U27-RA2)") (class "Default")
      (node (ref "J2") (pin "P$6") (pinfunction "P$6_P$6") (pintype "bidirectional"))
      (node (ref "U27") (pin "3") (pinfunction "RA2_3") (pintype "input"))
    )
    (net (code "184") (name "Net-(U27-RA3)") (class "Default")
      (node (ref "J2") (pin "P$2") (pinfunction "P$2_P$2") (pintype "bidirectional"))
      (node (ref "U27") (pin "4") (pinfunction "RA3_4") (pintype "input"))
    )
    (net (code "185") (name "Net-(U27-RA4)") (class "Default")
      (node (ref "J2") (pin "P$8") (pinfunction "P$8_P$8") (pintype "bidirectional"))
      (node (ref "U27") (pin "7") (pinfunction "RA4_7") (pintype "input"))
    )
    (net (code "186") (name "Net-(U27-RA5)") (class "Default")
      (node (ref "J2") (pin "P$9") (pinfunction "P$9_P$9") (pintype "bidirectional"))
      (node (ref "U27") (pin "9") (pinfunction "RA5_9") (pintype "input"))
    )
    (net (code "187") (name "Net-(U28B-O)") (class "Default")
      (node (ref "U28") (pin "10") (pinfunction "O_10") (pintype "output"))
      (node (ref "U28") (pin "9") (pinfunction "I_9") (pintype "input"))
    )
    (net (code "188") (name "Net-(U29-C+)") (class "Default")
      (node (ref "C38") (pin "+") (pinfunction "+_+") (pintype "passive"))
      (node (ref "U29") (pin "2") (pinfunction "C+_2") (pintype "bidirectional"))
    )
    (net (code "189") (name "Net-(U29-C-)") (class "Default")
      (node (ref "C38") (pin "-") (pinfunction "-_-") (pintype "passive"))
      (node (ref "U29") (pin "4") (pinfunction "C-_4") (pintype "bidirectional"))
    )
    (net (code "190") (name "RST") (class "Default")
      (node (ref "U24") (pin "39") (pinfunction "RESET_39") (pintype "input"))
      (node (ref "U25") (pin "39") (pinfunction "RESET_39") (pintype "input"))
      (node (ref "U28") (pin "1") (pinfunction "I_1") (pintype "input"))
      (node (ref "U28") (pin "6") (pinfunction "O_6") (pintype "output"))
    )
    (net (code "191") (name "SHIELD") (class "Default")
      (node (ref "J1") (pin "S1") (pinfunction "P$10_S1") (pintype "bidirectional"))
      (node (ref "J1") (pin "S2") (pinfunction "P$10_S2") (pintype "bidirectional"))
      (node (ref "J2") (pin "S1") (pinfunction "P$10_S1") (pintype "bidirectional"))
      (node (ref "J2") (pin "S2") (pinfunction "P$10_S2") (pintype "bidirectional"))
      (node (ref "J3") (pin "G$1") (pinfunction "SHIELD_G$1") (pintype "bidirectional"))
      (node (ref "J3") (pin "G$2") (pinfunction "SHIELD_G$2") (pintype "bidirectional"))
      (node (ref "J3") (pin "G$3") (pinfunction "SHIELD_G$3") (pintype "bidirectional"))
      (node (ref "JP4") (pin "2") (pinfunction "2_2") (pintype "passive"))
      (node (ref "JP5") (pin "2") (pinfunction "2_2") (pintype "passive"))
      (node (ref "JP6") (pin "2") (pinfunction "2_2") (pintype "passive"))
      (node (ref "JP7") (pin "2") (pinfunction "2_2") (pintype "passive"))
    )
    (net (code "192") (name "VCC") (class "Default")
      (node (ref "C1") (pin "P$1") (pinfunction "1_P$1") (pintype "passive"))
      (node (ref "C10") (pin "P$1") (pinfunction "1_P$1") (pintype "passive"))
      (node (ref "C11") (pin "P$1") (pinfunction "1_P$1") (pintype "passive"))
      (node (ref "C12") (pin "P$1") (pinfunction "1_P$1") (pintype "passive"))
      (node (ref "C13") (pin "P$1") (pinfunction "1_P$1") (pintype "passive"))
      (node (ref "C14") (pin "P$1") (pinfunction "1_P$1") (pintype "passive"))
      (node (ref "C15") (pin "P$1") (pinfunction "1_P$1") (pintype "passive"))
      (node (ref "C16") (pin "P$1") (pinfunction "1_P$1") (pintype "passive"))
      (node (ref "C17") (pin "P$1") (pinfunction "1_P$1") (pintype "passive"))
      (node (ref "C18") (pin "P$1") (pinfunction "1_P$1") (pintype "passive"))
      (node (ref "C19") (pin "P$1") (pinfunction "1_P$1") (pintype "passive"))
      (node (ref "C2") (pin "P$1") (pinfunction "1_P$1") (pintype "passive"))
      (node (ref "C20") (pin "P$1") (pinfunction "1_P$1") (pintype "passive"))
      (node (ref "C21") (pin "P$1") (pinfunction "1_P$1") (pintype "passive"))
      (node (ref "C22") (pin "P$1") (pinfunction "1_P$1") (pintype "passive"))
      (node (ref "C23") (pin "P$1") (pinfunction "1_P$1") (pintype "passive"))
      (node (ref "C24") (pin "P$1") (pinfunction "1_P$1") (pintype "passive"))
      (node (ref "C25") (pin "P$1") (pinfunction "1_P$1") (pintype "passive"))
      (node (ref "C26") (pin "P$1") (pinfunction "1_P$1") (pintype "passive"))
      (node (ref "C27") (pin "P$1") (pinfunction "1_P$1") (pintype "passive"))
      (node (ref "C28") (pin "P$1") (pinfunction "1_P$1") (pintype "passive"))
      (node (ref "C3") (pin "P$1") (pinfunction "1_P$1") (pintype "passive"))
      (node (ref "C31") (pin "+") (pinfunction "+_+") (pintype "passive"))
      (node (ref "C32") (pin "P$1") (pinfunction "1_P$1") (pintype "passive"))
      (node (ref "C33") (pin "P$1") (pinfunction "1_P$1") (pintype "passive"))
      (node (ref "C4") (pin "P$1") (pinfunction "1_P$1") (pintype "passive"))
      (node (ref "C5") (pin "P$1") (pinfunction "1_P$1") (pintype "passive"))
      (node (ref "C6") (pin "P$1") (pinfunction "1_P$1") (pintype "passive"))
      (node (ref "C7") (pin "P$1") (pinfunction "1_P$1") (pintype "passive"))
      (node (ref "C8") (pin "P$1") (pinfunction "1_P$1") (pintype "passive"))
      (node (ref "C9") (pin "P$1") (pinfunction "1_P$1") (pintype "passive"))
      (node (ref "CE0") (pin "5") (pinfunction "+5V_5") (pintype "bidirectional"))
      (node (ref "CE0") (pin "6") (pinfunction "+5V_6") (pintype "bidirectional"))
      (node (ref "J3") (pin "4") (pinfunction "4_4") (pintype "bidirectional"))
      (node (ref "R1") (pin "2") (pinfunction "2_2") (pintype "passive"))
      (node (ref "R4") (pin "2") (pinfunction "2_2") (pintype "passive"))
      (node (ref "R6") (pin "2") (pinfunction "2_2") (pintype "passive"))
      (node (ref "R7") (pin "1") (pinfunction "1_1") (pintype "passive"))
      (node (ref "RN1") (pin "1") (pinfunction "1_1") (pintype "passive"))
      (node (ref "U1") (pin "4") (pinfunction "/RES_4") (pintype "input"))
      (node (ref "U1") (pin "8") (pinfunction "VCC+_8") (pintype "power_in"))
      (node (ref "U14") (pin "10") (pinfunction "PRE_10") (pintype "input"))
      (node (ref "U14") (pin "12") (pinfunction "D_12") (pintype "input"))
      (node (ref "U14") (pin "2") (pinfunction "D_2") (pintype "input"))
      (node (ref "U14") (pin "4") (pinfunction "PRE_4") (pintype "input"))
      (node (ref "U2") (pin "10") (pinfunction "I1_10") (pintype "input"))
      (node (ref "U2") (pin "12") (pinfunction "I0_12") (pintype "input"))
      (node (ref "U2") (pin "13") (pinfunction "I1_13") (pintype "input"))
      (node (ref "U2") (pin "4") (pinfunction "I0_4") (pintype "input"))
      (node (ref "U2") (pin "5") (pinfunction "I1_5") (pintype "input"))
      (node (ref "U2") (pin "9") (pinfunction "I0_9") (pintype "input"))
      (node (ref "U20") (pin "10") (pinfunction "SER_10") (pintype "input"))
      (node (ref "U20") (pin "11") (pinfunction "A_11") (pintype "input"))
      (node (ref "U20") (pin "12") (pinfunction "B_12") (pintype "input"))
      (node (ref "U20") (pin "13") (pinfunction "C_13") (pintype "input"))
      (node (ref "U20") (pin "14") (pinfunction "D_14") (pintype "input"))
      (node (ref "U20") (pin "3") (pinfunction "E_3") (pintype "input"))
      (node (ref "U22") (pin "5") (pinfunction "I_5") (pintype "input"))
      (node (ref "U26") (pin "20") (pinfunction "VCC_20") (pintype "power_in"))
      (node (ref "U27") (pin "20") (pinfunction "VCC_20") (pintype "power_in"))
      (node (ref "U28") (pin "3") (pinfunction "I_3") (pintype "input"))
      (node (ref "U4") (pin "1") (pinfunction "I_1") (pintype "input"))
      (node (ref "U5") (pin "2") (pinfunction "D_2") (pintype "input"))
      (node (ref "U5") (pin "4") (pinfunction "PRE_4") (pintype "input"))
      (node (ref "U6") (pin "10") (pinfunction "PRE_10") (pintype "input"))
      (node (ref "U6") (pin "12") (pinfunction "D_12") (pintype "input"))
      (node (ref "U6") (pin "4") (pinfunction "PRE_4") (pintype "input"))
      (node (ref "U7") (pin "12") (pinfunction "I0_12") (pintype "input"))
      (node (ref "U7") (pin "13") (pinfunction "I1_13") (pintype "input"))
      (node (ref "U8") (pin "16") (pinfunction "VCC_16") (pintype "power_in"))
      (node (ref "Y1") (pin "1") (pinfunction "OE_1") (pintype "input"))
      (node (ref "Y1") (pin "8") (pinfunction "VCC_8") (pintype "power_in"))
    )
    (net (code "193") (name "unconnected-(CE0-+3.3V-Pad2)") (class "Default")
      (node (ref "CE0") (pin "2") (pinfunction "+3.3V_2") (pintype "bidirectional"))
    )
    (net (code "194") (name "unconnected-(CE0-+5VSB-Pad8)") (class "Default")
      (node (ref "CE0") (pin "8") (pinfunction "+5VSB_8") (pintype "bidirectional"))
    )
    (net (code "195") (name "unconnected-(CE0--12V-Pad7)") (class "Default")
      (node (ref "CE0") (pin "7") (pinfunction "-12V_7") (pintype "bidirectional"))
    )
    (net (code "196") (name "unconnected-(CE0-A5-Pad28)") (class "Default")
      (node (ref "CE0") (pin "28") (pinfunction "A5_28") (pintype "bidirectional"))
    )
    (net (code "197") (name "unconnected-(CE0-A6-Pad29)") (class "Default")
      (node (ref "CE0") (pin "29") (pinfunction "A6_29") (pintype "bidirectional"))
    )
    (net (code "198") (name "unconnected-(CE0-A7-Pad30)") (class "Default")
      (node (ref "CE0") (pin "30") (pinfunction "A7_30") (pintype "bidirectional"))
    )
    (net (code "199") (name "unconnected-(CE0-A8-Pad31)") (class "Default")
      (node (ref "CE0") (pin "31") (pinfunction "A8_31") (pintype "bidirectional"))
    )
    (net (code "200") (name "unconnected-(CE0-A9-Pad32)") (class "Default")
      (node (ref "CE0") (pin "32") (pinfunction "A9_32") (pintype "bidirectional"))
    )
    (net (code "201") (name "unconnected-(CE0-A10-Pad33)") (class "Default")
      (node (ref "CE0") (pin "33") (pinfunction "A10_33") (pintype "bidirectional"))
    )
    (net (code "202") (name "unconnected-(CE0-A11-Pad34)") (class "Default")
      (node (ref "CE0") (pin "34") (pinfunction "A11_34") (pintype "bidirectional"))
    )
    (net (code "203") (name "unconnected-(CE0-A12-Pad35)") (class "Default")
      (node (ref "CE0") (pin "35") (pinfunction "A12_35") (pintype "bidirectional"))
    )
    (net (code "204") (name "unconnected-(CE0-A13-Pad36)") (class "Default")
      (node (ref "CE0") (pin "36") (pinfunction "A13_36") (pintype "bidirectional"))
    )
    (net (code "205") (name "unconnected-(CE0-A14-Pad37)") (class "Default")
      (node (ref "CE0") (pin "37") (pinfunction "A14_37") (pintype "bidirectional"))
    )
    (net (code "206") (name "unconnected-(CE0-A15-Pad38)") (class "Default")
      (node (ref "CE0") (pin "38") (pinfunction "A15_38") (pintype "bidirectional"))
    )
    (net (code "207") (name "unconnected-(CE0-A16-Pad39)") (class "Default")
      (node (ref "CE0") (pin "39") (pinfunction "A16_39") (pintype "bidirectional"))
    )
    (net (code "208") (name "unconnected-(CE0-A17-Pad40)") (class "Default")
      (node (ref "CE0") (pin "40") (pinfunction "A17_40") (pintype "bidirectional"))
    )
    (net (code "209") (name "unconnected-(CE0-A18-Pad41)") (class "Default")
      (node (ref "CE0") (pin "41") (pinfunction "A18_41") (pintype "bidirectional"))
    )
    (net (code "210") (name "unconnected-(CE0-A19-Pad42)") (class "Default")
      (node (ref "CE0") (pin "42") (pinfunction "A19_42") (pintype "bidirectional"))
    )
    (net (code "211") (name "unconnected-(CE0-CLK-Pad15)") (class "Default")
      (node (ref "CE0") (pin "15") (pinfunction "CLK_15") (pintype "bidirectional"))
    )
    (net (code "212") (name "unconnected-(CE0-~{BUSACK}-Pad20)") (class "Default")
      (node (ref "CE0") (pin "20") (pinfunction "~{BUSACK}_20") (pintype "bidirectional"))
    )
    (net (code "213") (name "unconnected-(CE0-~{BUSRQ}-Pad10)") (class "Default")
      (node (ref "CE0") (pin "10") (pinfunction "~{BUSRQ}_10") (pintype "bidirectional"))
    )
    (net (code "214") (name "unconnected-(CE0-~{CBR}-Pad12)") (class "Default")
      (node (ref "CE0") (pin "12") (pinfunction "~{CBR}_12") (pintype "bidirectional"))
    )
    (net (code "215") (name "unconnected-(CE0-~{CINH}-Pad13)") (class "Default")
      (node (ref "CE0") (pin "13") (pinfunction "~{CINH}_13") (pintype "bidirectional"))
    )
    (net (code "216") (name "unconnected-(CE0-~{FETCH}-Pad19)") (class "Default")
      (node (ref "CE0") (pin "19") (pinfunction "~{FETCH}_19") (pintype "bidirectional"))
    )
    (net (code "217") (name "unconnected-(CE0-~{HALT}-Pad17)") (class "Default")
      (node (ref "CE0") (pin "17") (pinfunction "~{HALT}_17") (pintype "bidirectional"))
    )
    (net (code "218") (name "unconnected-(CE0-~{INH}-Pad11)") (class "Default")
      (node (ref "CE0") (pin "11") (pinfunction "~{INH}_11") (pintype "bidirectional"))
    )
    (net (code "219") (name "unconnected-(CE0-~{INT}-Pad51)") (class "Default")
      (node (ref "CE0") (pin "51") (pinfunction "~{INT}_51") (pintype "bidirectional"))
    )
    (net (code "220") (name "unconnected-(CE0-~{IOSEL}-Pad16)") (class "Default")
      (node (ref "CE0") (pin "16") (pinfunction "~{IOSEL}_16") (pintype "bidirectional"))
    )
    (net (code "221") (name "unconnected-(CE0-~{IRQ0}-Pad53)") (class "Default")
      (node (ref "CE0") (pin "53") (pinfunction "~{IRQ0}_53") (pintype "bidirectional"))
    )
    (net (code "222") (name "unconnected-(CE0-~{IRQ1}-Pad54)") (class "Default")
      (node (ref "CE0") (pin "54") (pinfunction "~{IRQ1}_54") (pintype "bidirectional"))
    )
    (net (code "223") (name "unconnected-(CE0-~{IRQ2}-Pad55)") (class "Default")
      (node (ref "CE0") (pin "55") (pinfunction "~{IRQ2}_55") (pintype "bidirectional"))
    )
    (net (code "224") (name "unconnected-(CE0-~{IRQ3}-Pad56)") (class "Default")
      (node (ref "CE0") (pin "56") (pinfunction "~{IRQ3}_56") (pintype "bidirectional"))
    )
    (net (code "225") (name "unconnected-(CE0-~{IRQ4}-Pad57)") (class "Default")
      (node (ref "CE0") (pin "57") (pinfunction "~{IRQ4}_57") (pintype "bidirectional"))
    )
    (net (code "226") (name "unconnected-(CE0-~{IRQ5}-Pad58)") (class "Default")
      (node (ref "CE0") (pin "58") (pinfunction "~{IRQ5}_58") (pintype "bidirectional"))
    )
    (net (code "227") (name "unconnected-(CE0-~{IRQ6}-Pad59)") (class "Default")
      (node (ref "CE0") (pin "59") (pinfunction "~{IRQ6}_59") (pintype "bidirectional"))
    )
    (net (code "228") (name "unconnected-(CE0-~{IRQ7}-Pad60)") (class "Default")
      (node (ref "CE0") (pin "60") (pinfunction "~{IRQ7}_60") (pintype "bidirectional"))
    )
    (net (code "229") (name "unconnected-(CE0-~{NMI}-Pad61)") (class "Default")
      (node (ref "CE0") (pin "61") (pinfunction "~{NMI}_61") (pintype "bidirectional"))
    )
    (net (code "230") (name "unconnected-(CE0-~{WAIT}-Pad18)") (class "Default")
      (node (ref "CE0") (pin "18") (pinfunction "~{WAIT}_18") (pintype "bidirectional"))
    )
    (net (code "231") (name "unconnected-(J3-Pad2)") (class "Default")
      (node (ref "J3") (pin "2") (pinfunction "2_2") (pintype "bidirectional"))
    )
    (net (code "232") (name "unconnected-(J3-Pad6)") (class "Default")
      (node (ref "J3") (pin "6") (pinfunction "6_6") (pintype "bidirectional"))
    )
    (net (code "233") (name "unconnected-(U2B-O-Pad6)") (class "Default")
      (node (ref "U2") (pin "6") (pinfunction "O_6") (pintype "output"))
    )
    (net (code "234") (name "unconnected-(U2C-O-Pad8)") (class "Default")
      (node (ref "U2") (pin "8") (pinfunction "O_8") (pintype "output"))
    )
    (net (code "235") (name "unconnected-(U2D-O-Pad11)") (class "Default")
      (node (ref "U2") (pin "11") (pinfunction "O_11") (pintype "output"))
    )
    (net (code "236") (name "unconnected-(U4A-O-Pad2)") (class "Default")
      (node (ref "U4") (pin "2") (pinfunction "O_2") (pintype "output"))
    )
    (net (code "237") (name "unconnected-(U5B-~{Q}-Pad8)") (class "Default")
      (node (ref "U5") (pin "8") (pinfunction "~{Q}_8") (pintype "output"))
    )
    (net (code "238") (name "unconnected-(U6A-~{Q}-Pad6)") (class "Default")
      (node (ref "U6") (pin "6") (pinfunction "~{Q}_6") (pintype "output"))
    )
    (net (code "239") (name "unconnected-(U6B-Q-Pad9)") (class "Default")
      (node (ref "U6") (pin "9") (pinfunction "Q_9") (pintype "output"))
    )
    (net (code "240") (name "unconnected-(U7D-O-Pad11)") (class "Default")
      (node (ref "U7") (pin "11") (pinfunction "O_11") (pintype "output"))
    )
    (net (code "241") (name "unconnected-(U8A-Y1-Pad14)") (class "Default")
      (node (ref "U8") (pin "14") (pinfunction "Y1_14") (pintype "output"))
    )
    (net (code "242") (name "unconnected-(U8A-Y2-Pad13)") (class "Default")
      (node (ref "U8") (pin "13") (pinfunction "Y2_13") (pintype "output"))
    )
    (net (code "243") (name "unconnected-(U8A-Y3-Pad12)") (class "Default")
      (node (ref "U8") (pin "12") (pinfunction "Y3_12") (pintype "output"))
    )
    (net (code "244") (name "unconnected-(U8A-Y4-Pad11)") (class "Default")
      (node (ref "U8") (pin "11") (pinfunction "Y4_11") (pintype "output"))
    )
    (net (code "245") (name "unconnected-(U8A-Y5-Pad10)") (class "Default")
      (node (ref "U8") (pin "10") (pinfunction "Y5_10") (pintype "output"))
    )
    (net (code "246") (name "unconnected-(U8A-Y6-Pad9)") (class "Default")
      (node (ref "U8") (pin "9") (pinfunction "Y6_9") (pintype "output"))
    )
    (net (code "247") (name "unconnected-(U8A-Y7-Pad7)") (class "Default")
      (node (ref "U8") (pin "7") (pinfunction "Y7_7") (pintype "output"))
    )
    (net (code "248") (name "unconnected-(U9A-Y2-Pad13)") (class "Default")
      (node (ref "U9") (pin "13") (pinfunction "Y2_13") (pintype "output"))
    )
    (net (code "249") (name "unconnected-(U9A-Y3-Pad12)") (class "Default")
      (node (ref "U9") (pin "12") (pinfunction "Y3_12") (pintype "output"))
    )
    (net (code "250") (name "unconnected-(U9A-Y4-Pad11)") (class "Default")
      (node (ref "U9") (pin "11") (pinfunction "Y4_11") (pintype "output"))
    )
    (net (code "251") (name "unconnected-(U9A-Y5-Pad10)") (class "Default")
      (node (ref "U9") (pin "10") (pinfunction "Y5_10") (pintype "output"))
    )
    (net (code "252") (name "unconnected-(U9A-Y6-Pad9)") (class "Default")
      (node (ref "U9") (pin "9") (pinfunction "Y6_9") (pintype "output"))
    )
    (net (code "253") (name "unconnected-(U10A-SEV-Pad5)") (class "Default")
      (node (ref "U10") (pin "5") (pinfunction "SEV_5") (pintype "output"))
    )
    (net (code "254") (name "unconnected-(U13A-QD-Pad6)") (class "Default")
      (node (ref "U13") (pin "6") (pinfunction "QD_6") (pintype "output"))
    )
    (net (code "255") (name "unconnected-(U13A-QE-Pad10)") (class "Default")
      (node (ref "U13") (pin "10") (pinfunction "QE_10") (pintype "output"))
    )
    (net (code "256") (name "unconnected-(U13A-QF-Pad11)") (class "Default")
      (node (ref "U13") (pin "11") (pinfunction "QF_11") (pintype "output"))
    )
    (net (code "257") (name "unconnected-(U13A-QG-Pad12)") (class "Default")
      (node (ref "U13") (pin "12") (pinfunction "QG_12") (pintype "output"))
    )
    (net (code "258") (name "unconnected-(U13A-QH-Pad13)") (class "Default")
      (node (ref "U13") (pin "13") (pinfunction "QH_13") (pintype "output"))
    )
    (net (code "259") (name "unconnected-(U14A-Q-Pad5)") (class "Default")
      (node (ref "U14") (pin "5") (pinfunction "Q_5") (pintype "output"))
    )
    (net (code "260") (name "unconnected-(U18A-SOD-Pad6)") (class "Default")
      (node (ref "U18") (pin "6") (pinfunction "SOD_6") (pintype "output"))
    )
    (net (code "261") (name "unconnected-(U20A-~{QH}-Pad7)") (class "Default")
      (node (ref "U20") (pin "7") (pinfunction "~{QH}_7") (pintype "output"))
    )
    (net (code "262") (name "unconnected-(U22C-O-Pad6)") (class "Default")
      (node (ref "U22") (pin "6") (pinfunction "O_6") (pintype "output"))
    )
    (net (code "263") (name "unconnected-(U24A-XTAL2-Pad19)") (class "Default")
      (node (ref "U24") (pin "19") (pinfunction "XTAL2_19") (pintype "output"))
    )
    (net (code "264") (name "unconnected-(U24A-~{DDIS}-Pad26)") (class "Default")
      (node (ref "U24") (pin "26") (pinfunction "~{DDIS}_26") (pintype "output"))
    )
    (net (code "265") (name "unconnected-(U24A-~{RXRDY}-Pad32)") (class "Default")
      (node (ref "U24") (pin "32") (pinfunction "~{RXRDY}_32") (pintype "output"))
    )
    (net (code "266") (name "unconnected-(U24A-~{TXRDY}-Pad27)") (class "Default")
      (node (ref "U24") (pin "27") (pinfunction "~{TXRDY}_27") (pintype "output"))
    )
    (net (code "267") (name "unconnected-(U25A-XTAL2-Pad19)") (class "Default")
      (node (ref "U25") (pin "19") (pinfunction "XTAL2_19") (pintype "output"))
    )
    (net (code "268") (name "unconnected-(U25A-~{DDIS}-Pad26)") (class "Default")
      (node (ref "U25") (pin "26") (pinfunction "~{DDIS}_26") (pintype "output"))
    )
    (net (code "269") (name "unconnected-(U25A-~{RXRDY}-Pad32)") (class "Default")
      (node (ref "U25") (pin "32") (pinfunction "~{RXRDY}_32") (pintype "output"))
    )
    (net (code "270") (name "unconnected-(U25A-~{TXRDY}-Pad27)") (class "Default")
      (node (ref "U25") (pin "27") (pinfunction "~{TXRDY}_27") (pintype "output"))
    )
    (net (code "271") (name "unconnected-(U28E-O-Pad4)") (class "Default")
      (node (ref "U28") (pin "4") (pinfunction "O_4") (pintype "output"))
    )
    (net (code "272") (name "unconnected-(U29-FREQX2-Pad6)") (class "Default")
      (node (ref "U29") (pin "6") (pinfunction "FREQX2_6") (pintype "bidirectional"))
    )
    (net (code "273") (name "unconnected-(U29-OSC-Pad7)") (class "Default")
      (node (ref "U29") (pin "7") (pinfunction "OSC_7") (pintype "bidirectional"))
    )
    (net (code "274") (name "unconnected-(U29-ZC-Pad1)") (class "Default")
      (node (ref "U29") (pin "1") (pinfunction "ZC_1") (pintype "bidirectional"))
    )
    (net (code "275") (name "~{BCSX}") (class "Default")
      (node (ref "CE0") (pin "9") (pinfunction "~{CSX}_9") (pintype "bidirectional"))
      (node (ref "U21") (pin "2") (pinfunction "A1_2") (pintype "input"))
    )
    (net (code "276") (name "~{BRD}") (class "Default")
      (node (ref "CE0") (pin "21") (pinfunction "~{RD}_21") (pintype "bidirectional"))
      (node (ref "U21") (pin "4") (pinfunction "A2_4") (pintype "input"))
    )
    (net (code "277") (name "~{BRST}") (class "Default")
      (node (ref "CE0") (pin "14") (pinfunction "~{RST}_14") (pintype "bidirectional"))
      (node (ref "U28") (pin "5") (pinfunction "I_5") (pintype "input"))
    )
    (net (code "278") (name "~{BWR}") (class "Default")
      (node (ref "CE0") (pin "22") (pinfunction "~{WR}_22") (pintype "bidirectional"))
      (node (ref "U21") (pin "17") (pinfunction "A4_17") (pintype "input"))
    )
    (net (code "279") (name "~{CSX}") (class "Default")
      (node (ref "U21") (pin "18") (pinfunction "Y1_18") (pintype "tri_state"))
      (node (ref "U23") (pin "19") (pinfunction "G_19") (pintype "input"))
      (node (ref "U24") (pin "16") (pinfunction "~{CS2}_16") (pintype "input"))
      (node (ref "U25") (pin "16") (pinfunction "~{CS2}_16") (pintype "input"))
      (node (ref "U8") (pin "4") (pinfunction "G2A_4") (pintype "input"))
      (node (ref "U9") (pin "4") (pinfunction "G2A_4") (pintype "input"))
    )
    (net (code "280") (name "~{CS_KBR}") (class "Default")
      (node (ref "U14") (pin "3") (pinfunction "CLK_3") (pintype "input"))
      (node (ref "U17") (pin "1") (pinfunction "G_1") (pintype "input"))
      (node (ref "U17") (pin "19") (pinfunction "G_19") (pintype "input"))
      (node (ref "U9") (pin "15") (pinfunction "Y0_15") (pintype "output"))
    )
    (net (code "281") (name "~{CS_KBW}") (class "Default")
      (node (ref "U19") (pin "1") (pinfunction "SH/~{LD}_1") (pintype "input"))
      (node (ref "U20") (pin "1") (pinfunction "SH/~{LD}_1") (pintype "input"))
      (node (ref "U5") (pin "10") (pinfunction "PRE_10") (pintype "input"))
      (node (ref "U5") (pin "3") (pinfunction "CLK_3") (pintype "input"))
      (node (ref "U8") (pin "15") (pinfunction "Y0_15") (pintype "output"))
    )
    (net (code "282") (name "~{INT_KB}") (class "Default")
      (node (ref "JP3") (pin "1") (pinfunction "1_1") (pintype "passive"))
      (node (ref "U14") (pin "8") (pinfunction "~{Q}_8") (pintype "output"))
    )
    (net (code "283") (name "~{IRQX}") (class "Default")
      (node (ref "CE0") (pin "52") (pinfunction "~{IRQX}_52") (pintype "bidirectional"))
      (node (ref "U22") (pin "12") (pinfunction "O_12") (pintype "output"))
    )
    (net (code "284") (name "~{KB_DATA}") (class "Default")
      (node (ref "U12") (pin "1") (pinfunction "A_1") (pintype "input"))
      (node (ref "U28") (pin "12") (pinfunction "O_12") (pintype "output"))
      (node (ref "U3") (pin "9") (pinfunction "I0_9") (pintype "input"))
    )
    (net (code "285") (name "~{KB_WRCYCLE}") (class "Default")
      (node (ref "U12") (pin "2") (pinfunction "B_2") (pintype "input"))
      (node (ref "U13") (pin "2") (pinfunction "B_2") (pintype "input"))
      (node (ref "U19") (pin "15") (pinfunction "INH_15") (pintype "input"))
      (node (ref "U20") (pin "15") (pinfunction "INH_15") (pintype "input"))
      (node (ref "U5") (pin "6") (pinfunction "~{Q}_6") (pintype "output"))
    )
    (net (code "286") (name "~{RD}") (class "Default")
      (node (ref "U21") (pin "16") (pinfunction "Y2_16") (pintype "tri_state"))
      (node (ref "U23") (pin "1") (pinfunction "DIR_1") (pintype "input"))
      (node (ref "U24") (pin "24") (pinfunction "~{IOR}_24") (pintype "input"))
      (node (ref "U25") (pin "24") (pinfunction "~{IOR}_24") (pintype "input"))
      (node (ref "U9") (pin "5") (pinfunction "G2B_5") (pintype "input"))
    )
    (net (code "287") (name "~{RST}") (class "Default")
      (node (ref "U11") (pin "1") (pinfunction "CLR_1") (pintype "input"))
      (node (ref "U28") (pin "2") (pinfunction "O_2") (pintype "output"))
      (node (ref "U5") (pin "13") (pinfunction "CLR_13") (pintype "input"))
      (node (ref "U6") (pin "1") (pinfunction "CLR_1") (pintype "input"))
      (node (ref "U7") (pin "1") (pinfunction "I0_1") (pintype "input"))
      (node (ref "U7") (pin "4") (pinfunction "I0_4") (pintype "input"))
    )
    (net (code "288") (name "~{WR}") (class "Default")
      (node (ref "U21") (pin "3") (pinfunction "Y4_3") (pintype "tri_state"))
      (node (ref "U24") (pin "20") (pinfunction "~{IOW}_20") (pintype "input"))
      (node (ref "U25") (pin "20") (pinfunction "~{IOW}_20") (pintype "input"))
      (node (ref "U8") (pin "5") (pinfunction "G2B_5") (pintype "input"))
    )
  )
)
